# S7G7_footprint_simplified_w_ethernet_v1p.net
KiCad netlist of a schematic drawn in EAGLE
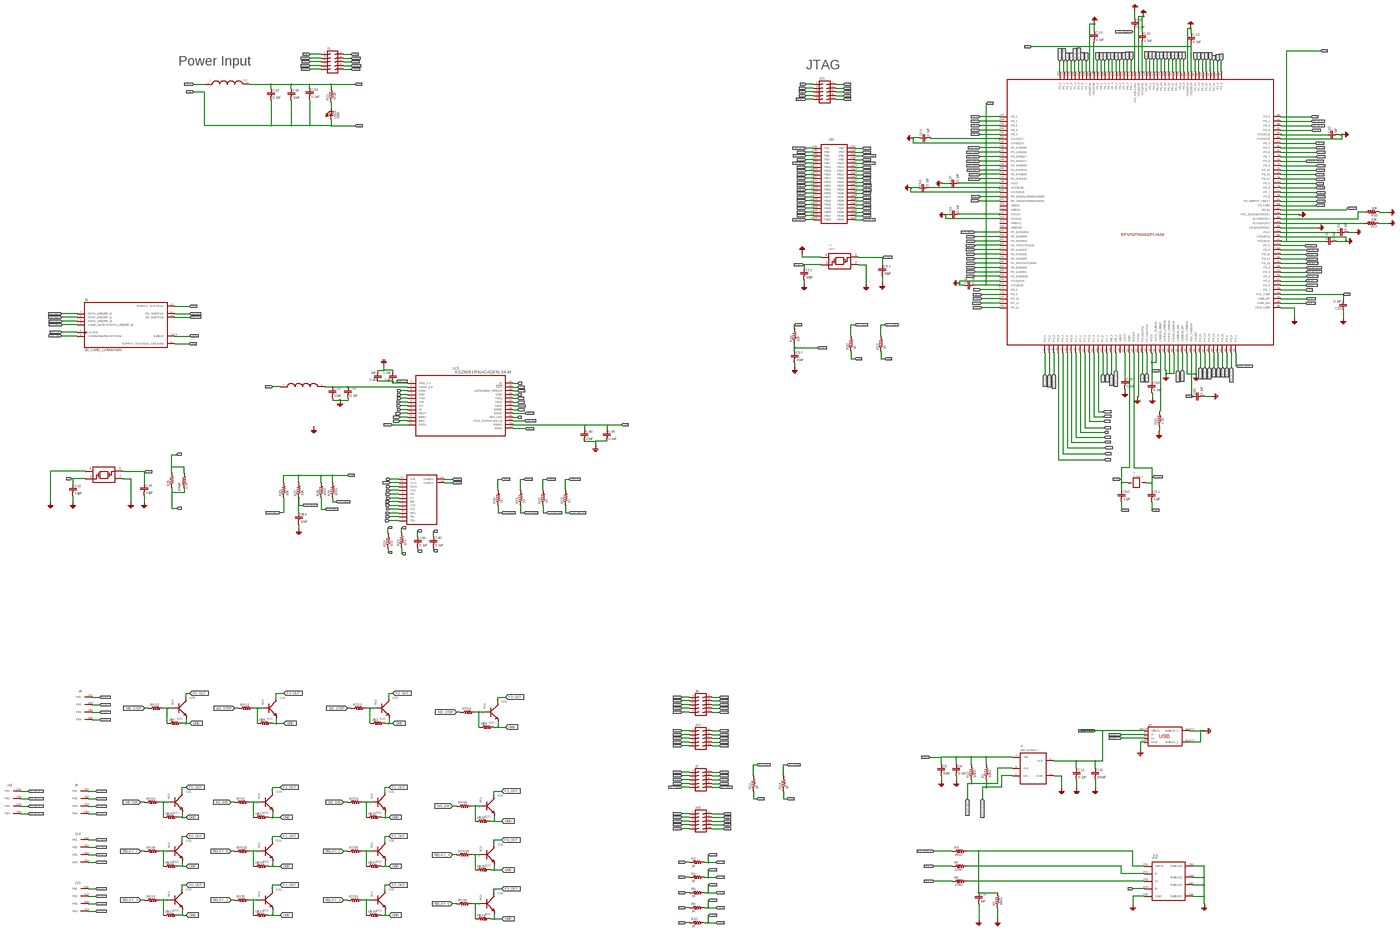
[diagram p0: schematic, sheet 1, overview]
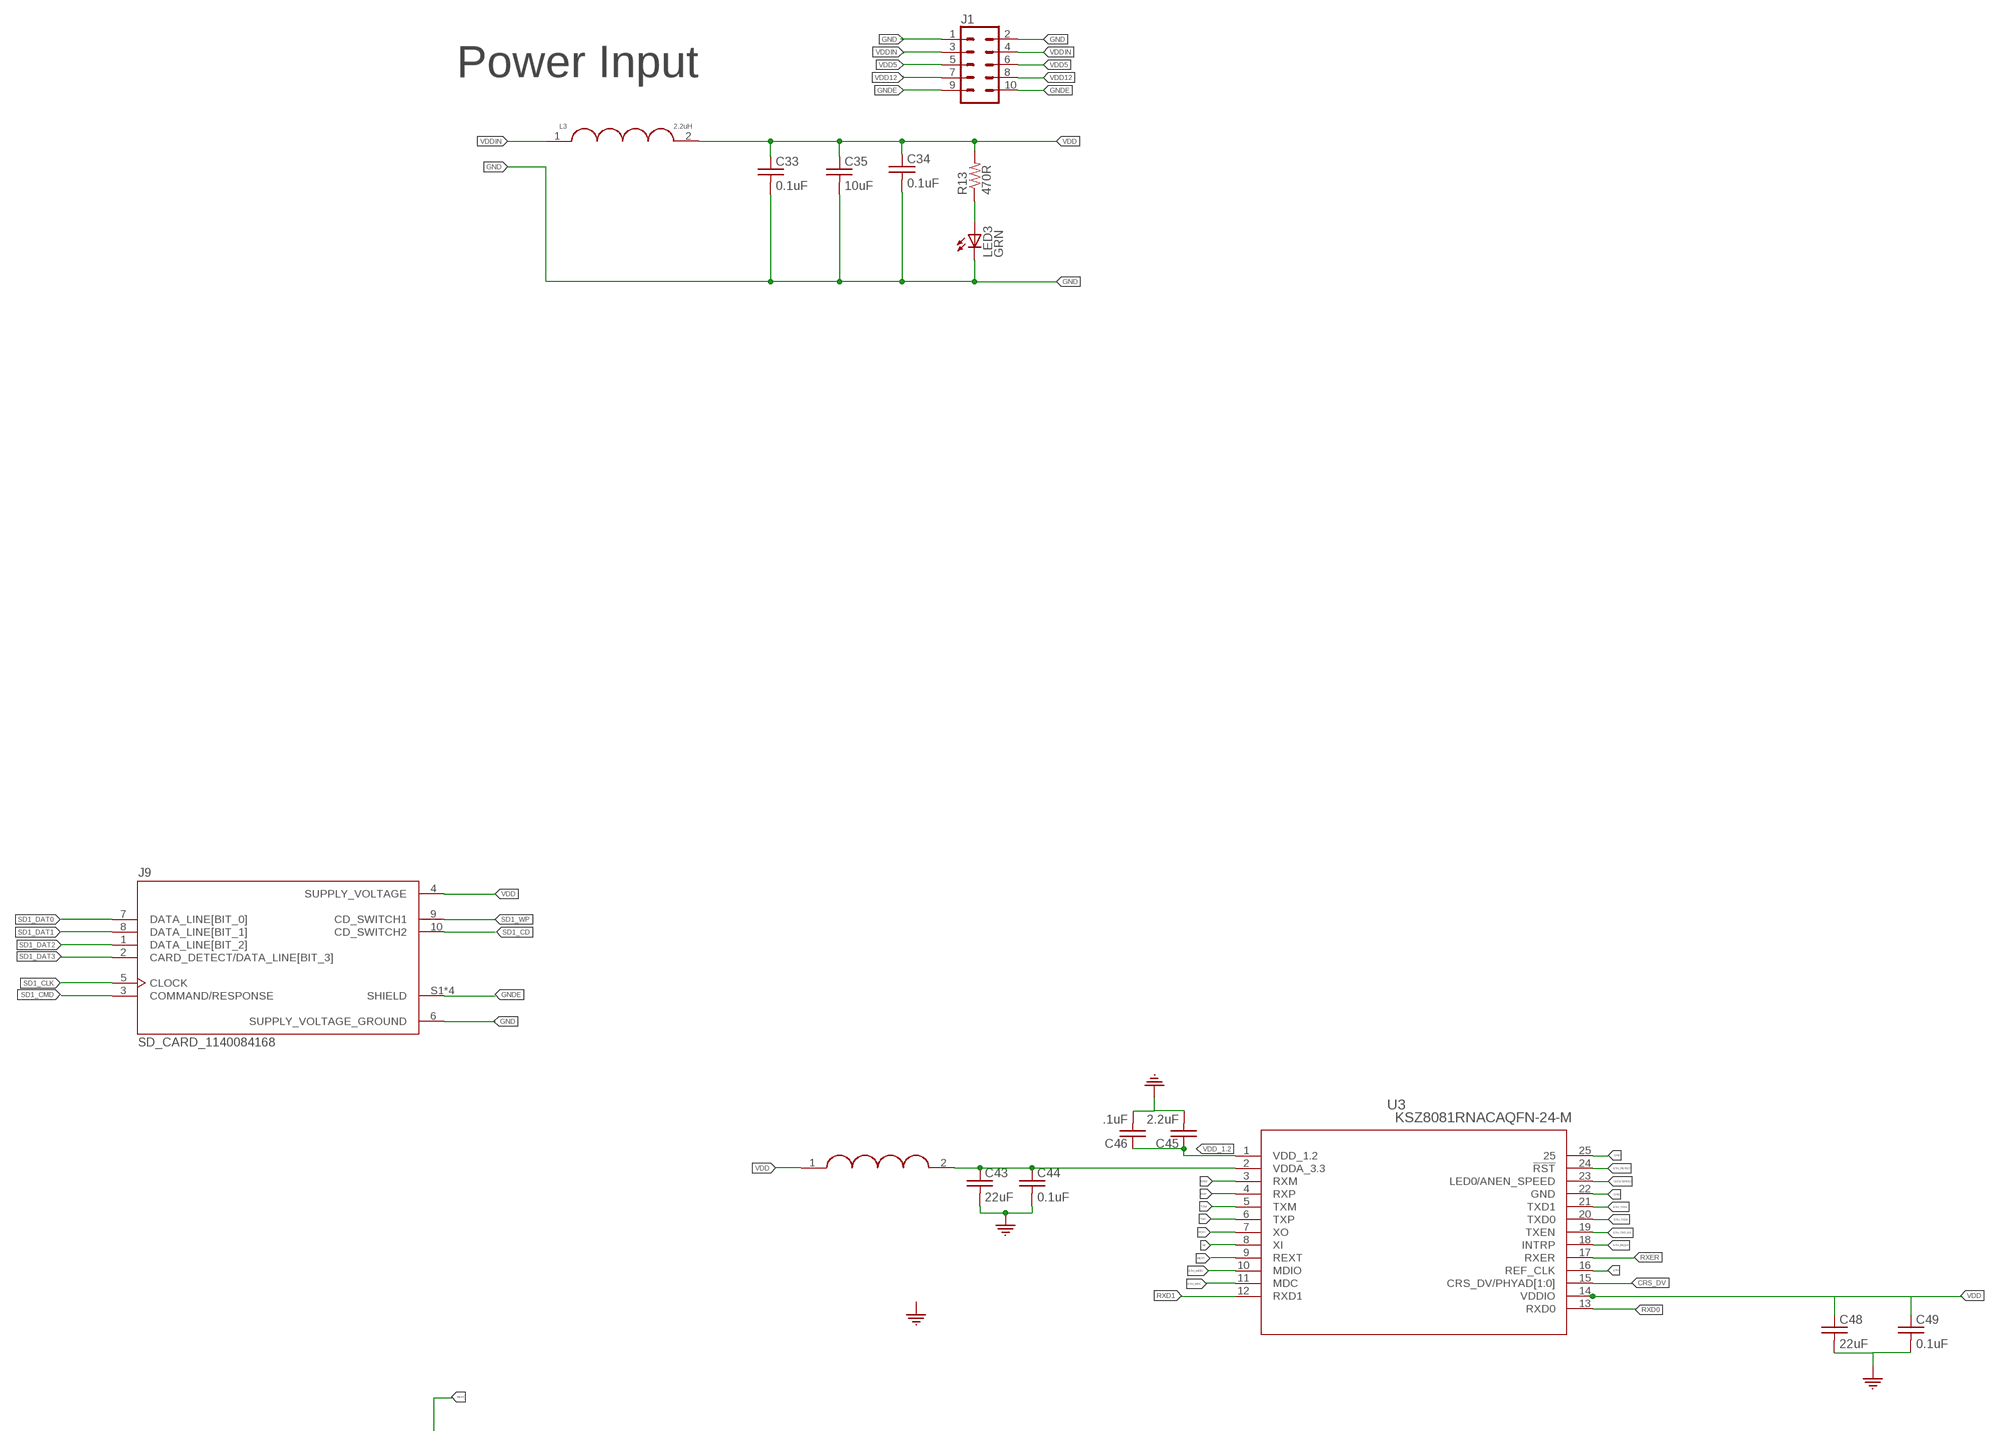
[diagram p1: schematic, sheet 1, part 1 of 4]
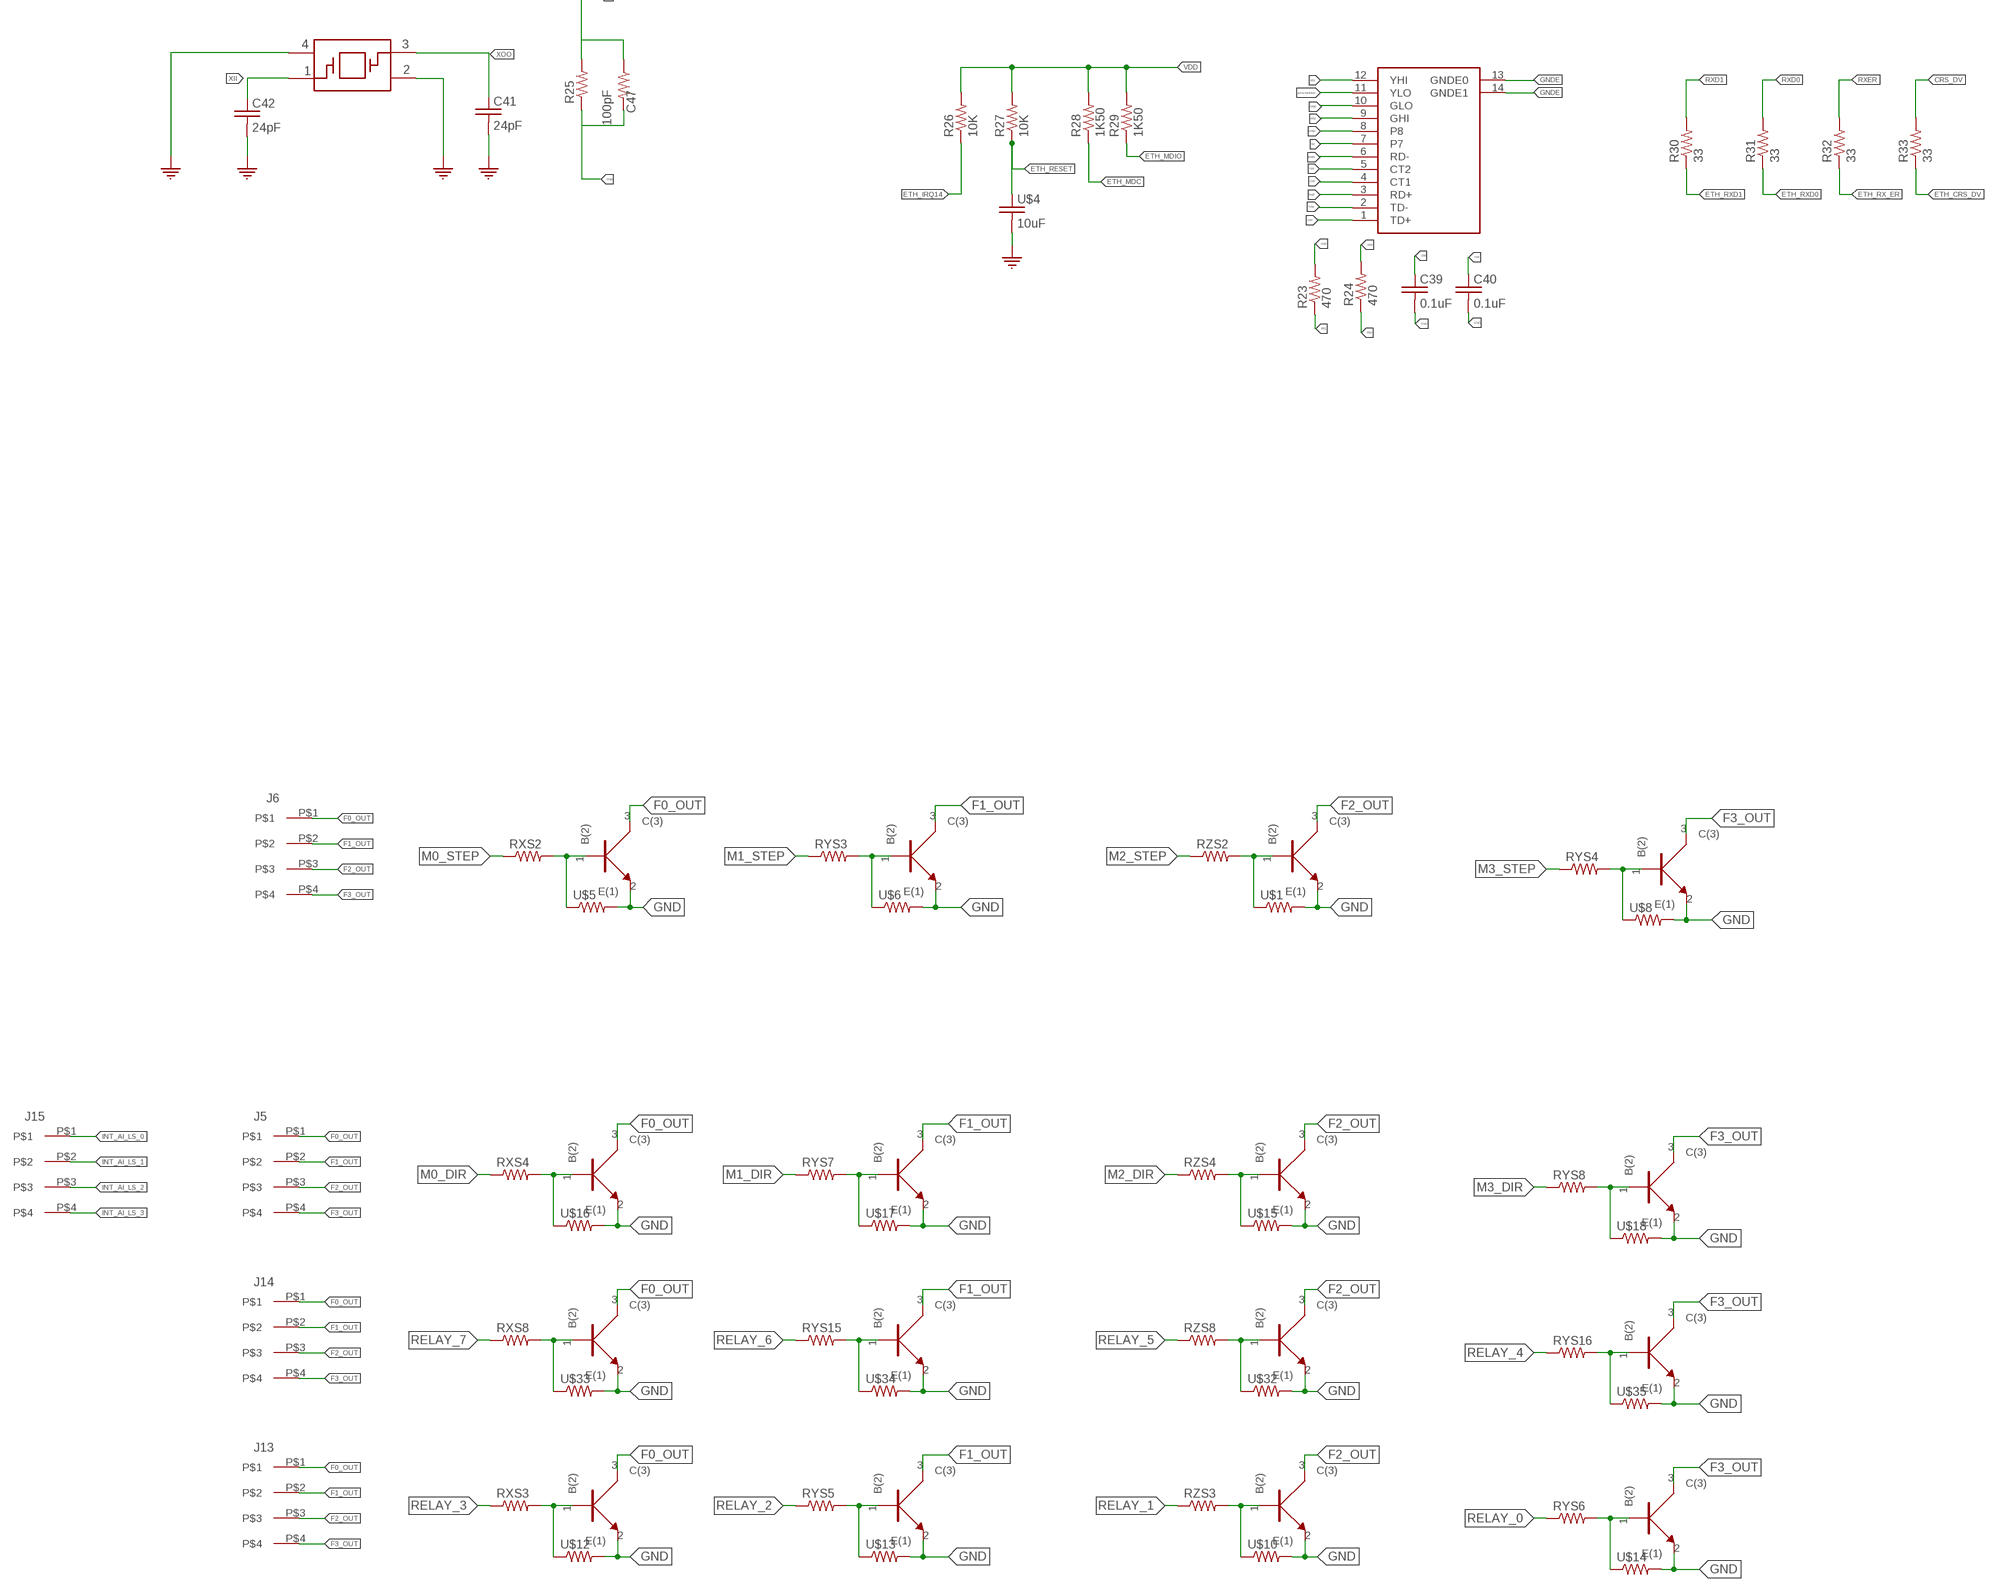
[diagram p2: schematic, sheet 1, part 2 of 4]
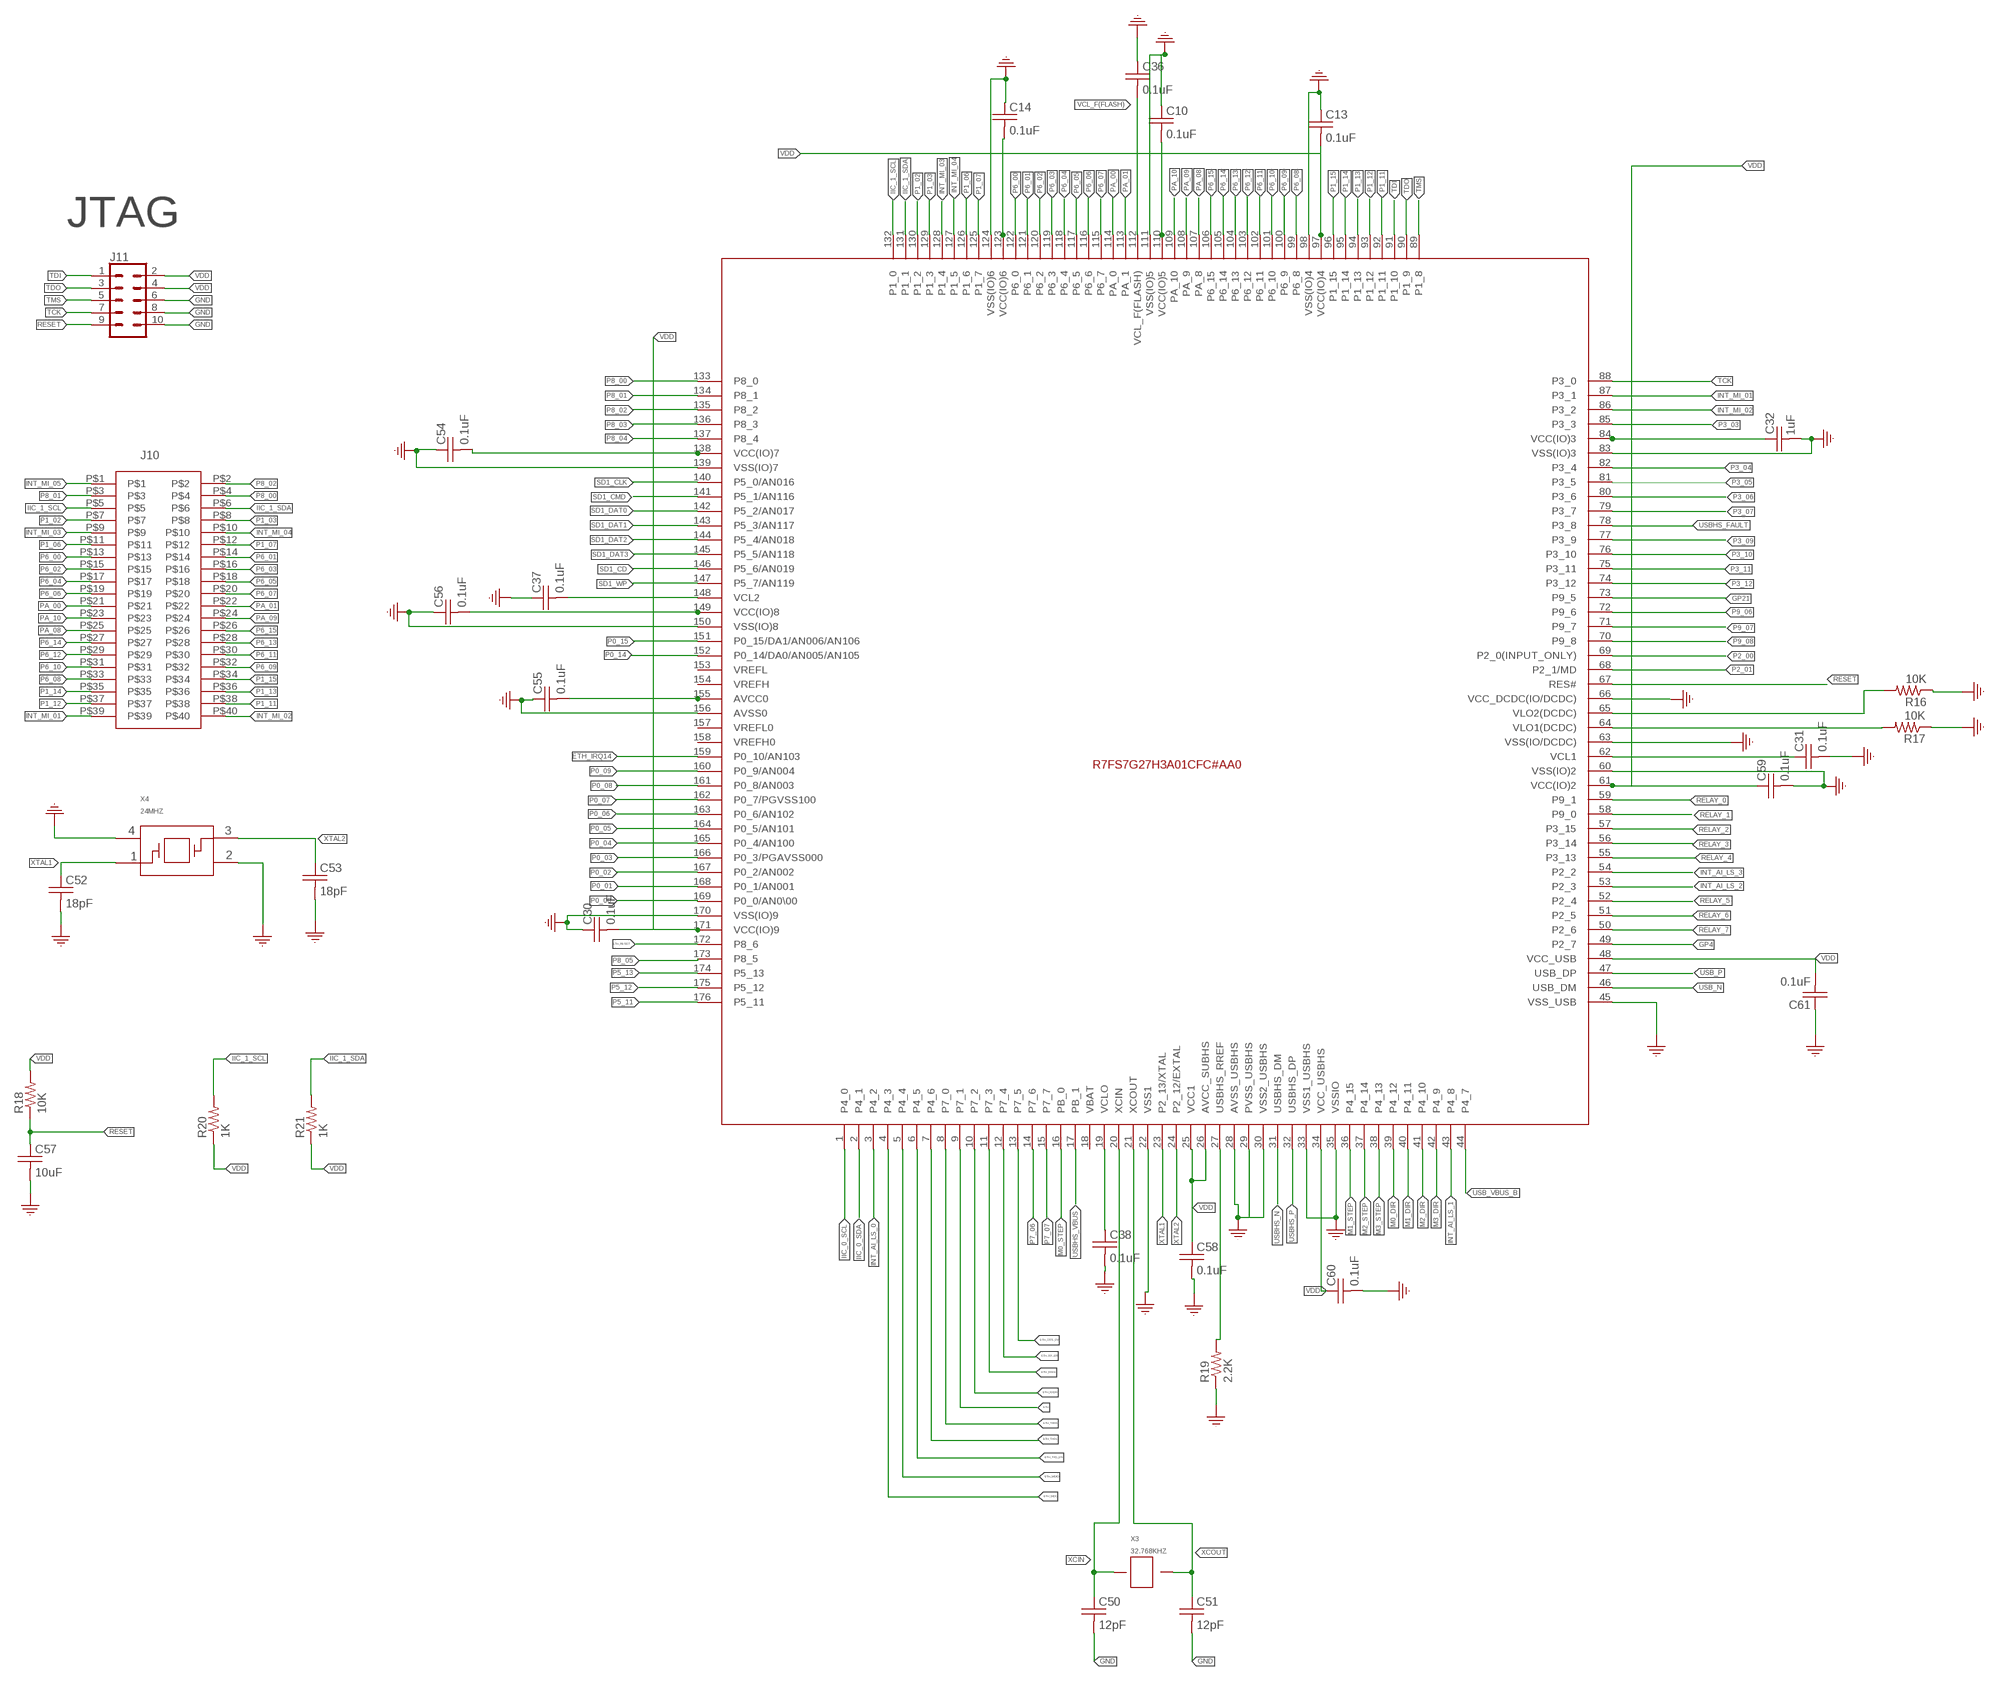
[diagram p3: schematic, sheet 1, part 3 of 4]
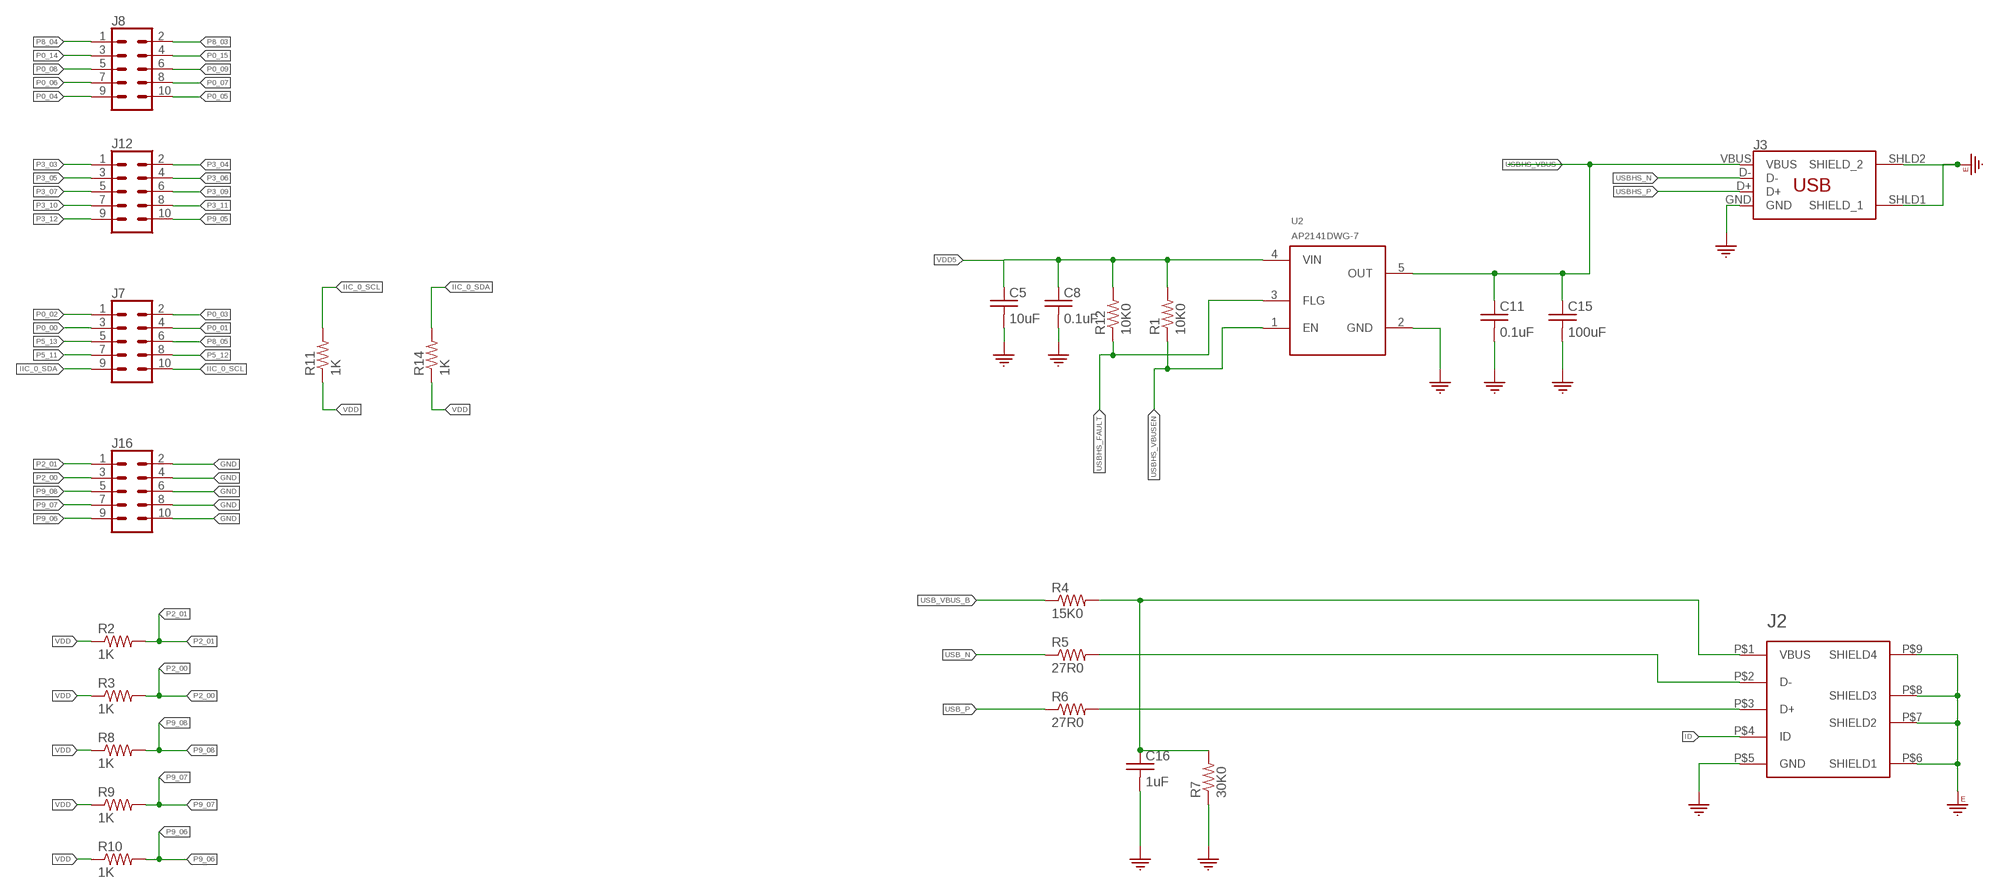
[diagram p4: schematic, sheet 1, part 4 of 4]

(export (version "E")
  (design (tool "Eeschema 10.0.6"))
  (components
    (comp (ref "C5")
      (value "10uF")
      (footprint "eagle-import:0402")
      (libsource (lib "eagle-import") (part "C_0402"))
    )
    (comp (ref "C8")
      (value "0.1uF")
      (footprint "eagle-import:0402")
      (libsource (lib "eagle-import") (part "C_0402"))
    )
    (comp (ref "C10")
      (value "0.1uF")
      (footprint "eagle-import:0402")
      (libsource (lib "eagle-import") (part "C_0402"))
    )
    (comp (ref "C11")
      (value "0.1uF")
      (footprint "eagle-import:0402")
      (libsource (lib "eagle-import") (part "C_0402"))
    )
    (comp (ref "C13")
      (value "0.1uF")
      (footprint "eagle-import:0402")
      (libsource (lib "eagle-import") (part "C_0402"))
    )
    (comp (ref "C14")
      (value "0.1uF")
      (footprint "eagle-import:0402")
      (libsource (lib "eagle-import") (part "C_0402"))
    )
    (comp (ref "C15")
      (value "100uF")
      (footprint "eagle-import:C1210")
      (libsource (lib "eagle-import") (part "C_1210"))
    )
    (comp (ref "C16")
      (value "1uF")
      (footprint "eagle-import:0402")
      (libsource (lib "eagle-import") (part "C_0402"))
    )
    (comp (ref "C30")
      (value "0.1uF")
      (footprint "eagle-import:0402")
      (libsource (lib "eagle-import") (part "C_0402"))
    )
    (comp (ref "C31")
      (value "0.1uF")
      (footprint "eagle-import:0402")
      (libsource (lib "eagle-import") (part "C_0402"))
    )
    (comp (ref "C32")
      (value "1uF")
      (footprint "eagle-import:0402")
      (libsource (lib "eagle-import") (part "C_0402"))
    )
    (comp (ref "C33")
      (value "0.1uF")
      (footprint "eagle-import:0402")
      (libsource (lib "eagle-import") (part "C_0402"))
    )
    (comp (ref "C34")
      (value "0.1uF")
      (footprint "eagle-import:0402")
      (libsource (lib "eagle-import") (part "C_0402"))
    )
    (comp (ref "C35")
      (value "10uF")
      (footprint "eagle-import:0402")
      (libsource (lib "eagle-import") (part "C_0402"))
    )
    (comp (ref "C36")
      (value "0.1uF")
      (footprint "eagle-import:0402")
      (libsource (lib "eagle-import") (part "C_0402"))
    )
    (comp (ref "C37")
      (value "0.1uF")
      (footprint "eagle-import:0402")
      (libsource (lib "eagle-import") (part "C_0402"))
    )
    (comp (ref "C38")
      (value "0.1uF")
      (footprint "eagle-import:0402")
      (libsource (lib "eagle-import") (part "C_0402"))
    )
    (comp (ref "C39")
      (value "0.1uF")
      (footprint "eagle-import:0402")
      (libsource (lib "eagle-import") (part "C_0402"))
    )
    (comp (ref "C40")
      (value "0.1uF")
      (footprint "eagle-import:0402")
      (libsource (lib "eagle-import") (part "C_0402"))
    )
    (comp (ref "C41")
      (value "24pF")
      (footprint "eagle-import:0402")
      (libsource (lib "eagle-import") (part "C_0402"))
    )
    (comp (ref "C42")
      (value "24pF")
      (footprint "eagle-import:0402")
      (libsource (lib "eagle-import") (part "C_0402"))
    )
    (comp (ref "C43")
      (value "22uF")
      (footprint "eagle-import:0603")
      (libsource (lib "eagle-import") (part "C_0603"))
    )
    (comp (ref "C44")
      (value "0.1uF")
      (footprint "eagle-import:0402")
      (libsource (lib "eagle-import") (part "C_0402"))
    )
    (comp (ref "C45")
      (value "2.2uF")
      (footprint "eagle-import:0402")
      (libsource (lib "eagle-import") (part "C_0402"))
    )
    (comp (ref "C46")
      (value ".1uF")
      (footprint "eagle-import:0402")
      (libsource (lib "eagle-import") (part "C_0402"))
    )
    (comp (ref "C47")
      (value "100pF")
      (footprint "eagle-import:0402")
      (libsource (lib "eagle-import") (part "R_0402"))
    )
    (comp (ref "C48")
      (value "22uF")
      (footprint "eagle-import:0603")
      (libsource (lib "eagle-import") (part "C_0603"))
    )
    (comp (ref "C49")
      (value "0.1uF")
      (footprint "eagle-import:0402")
      (libsource (lib "eagle-import") (part "C_0402"))
    )
    (comp (ref "C50")
      (value "12pF")
      (footprint "eagle-import:0402")
      (libsource (lib "eagle-import") (part "C_0402"))
    )
    (comp (ref "C51")
      (value "12pF")
      (footprint "eagle-import:0402")
      (libsource (lib "eagle-import") (part "C_0402"))
    )
    (comp (ref "C52")
      (value "18pF")
      (footprint "eagle-import:0402")
      (libsource (lib "eagle-import") (part "C_0402"))
    )
    (comp (ref "C53")
      (value "18pF")
      (footprint "eagle-import:0402")
      (libsource (lib "eagle-import") (part "C_0402"))
    )
    (comp (ref "C54")
      (value "0.1uF")
      (footprint "eagle-import:0402")
      (libsource (lib "eagle-import") (part "C_0402"))
    )
    (comp (ref "C55")
      (value "0.1uF")
      (footprint "eagle-import:0402")
      (libsource (lib "eagle-import") (part "C_0402"))
    )
    (comp (ref "C56")
      (value "0.1uF")
      (footprint "eagle-import:0402")
      (libsource (lib "eagle-import") (part "C_0402"))
    )
    (comp (ref "C57")
      (value "10uF")
      (footprint "eagle-import:0402")
      (libsource (lib "eagle-import") (part "C_0402"))
    )
    (comp (ref "C58")
      (value "0.1uF")
      (footprint "eagle-import:0402")
      (libsource (lib "eagle-import") (part "C_0402"))
    )
    (comp (ref "C59")
      (value "0.1uF")
      (footprint "eagle-import:0402")
      (libsource (lib "eagle-import") (part "C_0402"))
    )
    (comp (ref "C60")
      (value "0.1uF")
      (footprint "eagle-import:0402")
      (libsource (lib "eagle-import") (part "C_0402"))
    )
    (comp (ref "C61")
      (value "0.1uF")
      (footprint "eagle-import:0402")
      (libsource (lib "eagle-import") (part "C_0402"))
    )
    (comp (ref "FB2/2")
      (value "FB_0805_120_OHM")
      (footprint "eagle-import:0805")
      (libsource (lib "eagle-import") (part "FB_0805_120_OHM"))
    )
    (comp (ref "J1")
      (value "CONN_05X2PTH")
      (footprint "eagle-import:2X5")
      (libsource (lib "eagle-import") (part "CONN_05X2PTH"))
    )
    (comp (ref "J2")
      (value "USB_MICRO-B")
      (footprint "eagle-import:USB_MICRO-B")
      (libsource (lib "eagle-import") (part "USB_MICRO-B"))
    )
    (comp (ref "J3")
      (value "USB_A")
      (footprint "eagle-import:USB_A_SMT")
      (libsource (lib "eagle-import") (part "USB_A"))
    )
    (comp (ref "J4")
      (value "RJ45_WITH_ELEC")
      (footprint "eagle-import:RJ45_TH_ELEC")
      (libsource (lib "eagle-import") (part "RJ45_WITH_ELEC"))
    )
    (comp (ref "J5")
      (value "3.81MM_1_X_4_RT_ANGLE_PLUG_HEADER")
      (footprint "eagle-import:1X4_3.81MM_PITCH")
      (libsource (lib "eagle-import") (part "3.81MM_1_X_4_RT_ANGLE_PLUG_HEADER"))
    )
    (comp (ref "J6")
      (value "3.81MM_1_X_4_RT_ANGLE_PLUG_HEADER")
      (footprint "eagle-import:1X4_3.81MM_PITCH")
      (libsource (lib "eagle-import") (part "3.81MM_1_X_4_RT_ANGLE_PLUG_HEADER"))
    )
    (comp (ref "J7")
      (value "CONN_05X2NO_SILK")
      (footprint "eagle-import:2X5_NOSILK")
      (libsource (lib "eagle-import") (part "CONN_05X2NO_SILK"))
    )
    (comp (ref "J8")
      (value "CONN_05X2NO_SILK")
      (footprint "eagle-import:2X5_NOSILK")
      (libsource (lib "eagle-import") (part "CONN_05X2NO_SILK"))
    )
    (comp (ref "J9")
      (value "SD_CARD_1140084168")
      (footprint "eagle-import:AMPHENOL_1140084168")
      (fields
        (field (name "DIGI-KEY_PART_NUMBER") "114-00841-68-1-ND")
        (field (name "MF") "Amphenol ICC")
        (field (name "MP") "114-00841-68")
      )
      (libsource (lib "eagle-import") (part "SD_CARD_1140084168"))
    )
    (comp (ref "J10")
      (value "HEADER_2_X_20_GENERIC")
      (footprint "eagle-import:HEADER_2_X_20_.1_INCH")
      (libsource (lib "eagle-import") (part "HEADER_2_X_20_GENERIC"))
    )
    (comp (ref "J11")
      (value "CONN_05X2PTH")
      (footprint "eagle-import:2X5")
      (libsource (lib "eagle-import") (part "CONN_05X2PTH"))
    )
    (comp (ref "J12")
      (value "CONN_05X2NO_SILK")
      (footprint "eagle-import:2X5_NOSILK")
      (libsource (lib "eagle-import") (part "CONN_05X2NO_SILK"))
    )
    (comp (ref "J13")
      (value "3.81MM_1_X_4_RT_ANGLE_PLUG_HEADER")
      (footprint "eagle-import:1X4_3.81MM_PITCH")
      (libsource (lib "eagle-import") (part "3.81MM_1_X_4_RT_ANGLE_PLUG_HEADER"))
    )
    (comp (ref "J14")
      (value "3.81MM_1_X_4_RT_ANGLE_PLUG_HEADER")
      (footprint "eagle-import:1X4_3.81MM_PITCH")
      (libsource (lib "eagle-import") (part "3.81MM_1_X_4_RT_ANGLE_PLUG_HEADER"))
    )
    (comp (ref "J15")
      (value "3.81MM_1_X_4_RT_ANGLE_PLUG_HEADER")
      (footprint "eagle-import:1X4_3.81MM_PITCH")
      (libsource (lib "eagle-import") (part "3.81MM_1_X_4_RT_ANGLE_PLUG_HEADER"))
    )
    (comp (ref "J16")
      (value "CONN_05X2SHD_SMD")
      (footprint "eagle-import:2X5-SHROUDED_SMD")
      (libsource (lib "eagle-import") (part "CONN_05X2SHD_SMD"))
    )
    (comp (ref "L3")
      (value "2.2uH")
      (footprint "eagle-import:1008_(2520_METRIC)")
      (libsource (lib "eagle-import") (part "INDUCTOR_1008_2.2_MH_1.3A"))
    )
    (comp (ref "LED3")
      (value "LED_0805_GREEN")
      (footprint "eagle-import:LED_0805_GREEN")
      (libsource (lib "eagle-import") (part "LED_0805_GREEN"))
    )
    (comp (ref "R1")
      (value "10K0")
      (footprint "eagle-import:0402")
      (libsource (lib "eagle-import") (part "R_0402"))
    )
    (comp (ref "R2")
      (value "1K")
      (footprint "eagle-import:0402")
      (libsource (lib "eagle-import") (part "R_0402"))
    )
    (comp (ref "R3")
      (value "1K")
      (footprint "eagle-import:0402")
      (libsource (lib "eagle-import") (part "R_0402"))
    )
    (comp (ref "R4")
      (value "15K0")
      (footprint "eagle-import:0402")
      (libsource (lib "eagle-import") (part "R_0402"))
    )
    (comp (ref "R5")
      (value "27R0")
      (footprint "eagle-import:0402")
      (libsource (lib "eagle-import") (part "R_0402"))
    )
    (comp (ref "R6")
      (value "27R0")
      (footprint "eagle-import:0402")
      (libsource (lib "eagle-import") (part "R_0402"))
    )
    (comp (ref "R7")
      (value "30K0")
      (footprint "eagle-import:0402")
      (libsource (lib "eagle-import") (part "R_0402"))
    )
    (comp (ref "R8")
      (value "1K")
      (footprint "eagle-import:0402")
      (libsource (lib "eagle-import") (part "R_0402"))
    )
    (comp (ref "R9")
      (value "1K")
      (footprint "eagle-import:0402")
      (libsource (lib "eagle-import") (part "R_0402"))
    )
    (comp (ref "R10")
      (value "1K")
      (footprint "eagle-import:0402")
      (libsource (lib "eagle-import") (part "R_0402"))
    )
    (comp (ref "R11")
      (value "1K")
      (footprint "eagle-import:0402")
      (libsource (lib "eagle-import") (part "R_0402"))
    )
    (comp (ref "R12")
      (value "10K0")
      (footprint "eagle-import:0402")
      (libsource (lib "eagle-import") (part "R_0402"))
    )
    (comp (ref "R13")
      (value "470R")
      (footprint "eagle-import:0402")
      (libsource (lib "eagle-import") (part "R_0402"))
    )
    (comp (ref "R14")
      (value "1K")
      (footprint "eagle-import:0402")
      (libsource (lib "eagle-import") (part "R_0402"))
    )
    (comp (ref "R16")
      (value "10K")
      (footprint "eagle-import:0402")
      (libsource (lib "eagle-import") (part "R_0402"))
    )
    (comp (ref "R17")
      (value "10K")
      (footprint "eagle-import:0402")
      (libsource (lib "eagle-import") (part "R_0402"))
    )
    (comp (ref "R18")
      (value "10K")
      (footprint "eagle-import:0402")
      (libsource (lib "eagle-import") (part "R_0402"))
    )
    (comp (ref "R19")
      (value "2.2K")
      (footprint "eagle-import:0402")
      (libsource (lib "eagle-import") (part "R_0402"))
    )
    (comp (ref "R20")
      (value "1K")
      (footprint "eagle-import:0402")
      (libsource (lib "eagle-import") (part "R_0402"))
    )
    (comp (ref "R21")
      (value "1K")
      (footprint "eagle-import:0402")
      (libsource (lib "eagle-import") (part "R_0402"))
    )
    (comp (ref "R23")
      (value "470")
      (footprint "eagle-import:0402")
      (libsource (lib "eagle-import") (part "R_0402"))
    )
    (comp (ref "R24")
      (value "470")
      (footprint "eagle-import:0402")
      (libsource (lib "eagle-import") (part "R_0402"))
    )
    (comp (ref "R25")
      (value "6k49")
      (footprint "eagle-import:0402")
      (libsource (lib "eagle-import") (part "R_0402"))
    )
    (comp (ref "R26")
      (value "10K")
      (footprint "eagle-import:0402")
      (libsource (lib "eagle-import") (part "R_0402"))
    )
    (comp (ref "R27")
      (value "10K")
      (footprint "eagle-import:0402")
      (libsource (lib "eagle-import") (part "R_0402"))
    )
    (comp (ref "R28")
      (value "1K50")
      (footprint "eagle-import:0402")
      (libsource (lib "eagle-import") (part "R_0402"))
    )
    (comp (ref "R29")
      (value "1K50")
      (footprint "eagle-import:0402")
      (libsource (lib "eagle-import") (part "R_0402"))
    )
    (comp (ref "R30")
      (value "33")
      (footprint "eagle-import:0402")
      (libsource (lib "eagle-import") (part "R_0402"))
    )
    (comp (ref "R31")
      (value "33")
      (footprint "eagle-import:0402")
      (libsource (lib "eagle-import") (part "R_0402"))
    )
    (comp (ref "R32")
      (value "33")
      (footprint "eagle-import:0402")
      (libsource (lib "eagle-import") (part "R_0402"))
    )
    (comp (ref "R33")
      (value "33")
      (footprint "eagle-import:0402")
      (libsource (lib "eagle-import") (part "R_0402"))
    )
    (comp (ref "RXS2")
      (value "1K")
      (footprint "eagle-import:0402")
      (libsource (lib "eagle-import") (part "R_0402"))
    )
    (comp (ref "RXS3")
      (value "1K")
      (footprint "eagle-import:0402")
      (libsource (lib "eagle-import") (part "R_0402"))
    )
    (comp (ref "RXS4")
      (value "1K")
      (footprint "eagle-import:0402")
      (libsource (lib "eagle-import") (part "R_0402"))
    )
    (comp (ref "RXS8")
      (value "1K")
      (footprint "eagle-import:0402")
      (libsource (lib "eagle-import") (part "R_0402"))
    )
    (comp (ref "RYS3")
      (value "1K")
      (footprint "eagle-import:0402")
      (libsource (lib "eagle-import") (part "R_0402"))
    )
    (comp (ref "RYS4")
      (value "1K")
      (footprint "eagle-import:0402")
      (libsource (lib "eagle-import") (part "R_0402"))
    )
    (comp (ref "RYS5")
      (value "1K")
      (footprint "eagle-import:0402")
      (libsource (lib "eagle-import") (part "R_0402"))
    )
    (comp (ref "RYS6")
      (value "1K")
      (footprint "eagle-import:0402")
      (libsource (lib "eagle-import") (part "R_0402"))
    )
    (comp (ref "RYS7")
      (value "1K")
      (footprint "eagle-import:0402")
      (libsource (lib "eagle-import") (part "R_0402"))
    )
    (comp (ref "RYS8")
      (value "1K")
      (footprint "eagle-import:0402")
      (libsource (lib "eagle-import") (part "R_0402"))
    )
    (comp (ref "RYS15")
      (value "1K")
      (footprint "eagle-import:0402")
      (libsource (lib "eagle-import") (part "R_0402"))
    )
    (comp (ref "RYS16")
      (value "1K")
      (footprint "eagle-import:0402")
      (libsource (lib "eagle-import") (part "R_0402"))
    )
    (comp (ref "RZS2")
      (value "1K")
      (footprint "eagle-import:0402")
      (libsource (lib "eagle-import") (part "R_0402"))
    )
    (comp (ref "RZS3")
      (value "1K")
      (footprint "eagle-import:0402")
      (libsource (lib "eagle-import") (part "R_0402"))
    )
    (comp (ref "RZS4")
      (value "1K")
      (footprint "eagle-import:0402")
      (libsource (lib "eagle-import") (part "R_0402"))
    )
    (comp (ref "RZS8")
      (value "1K")
      (footprint "eagle-import:0402")
      (libsource (lib "eagle-import") (part "R_0402"))
    )
    (comp (ref "U$1")
      (value "1K")
      (footprint "eagle-import:0402")
      (libsource (lib "eagle-import") (part "R_0402"))
    )
    (comp (ref "U$3")
      (value "XTAL_25_MHZ")
      (footprint "eagle-import:SMD_3225")
      (libsource (lib "eagle-import") (part "XTAL_25_MHZ"))
    )
    (comp (ref "U$4")
      (value "10uF")
      (footprint "eagle-import:0402")
      (libsource (lib "eagle-import") (part "C_0402"))
    )
    (comp (ref "U$5")
      (value "1K")
      (footprint "eagle-import:0402")
      (libsource (lib "eagle-import") (part "R_0402"))
    )
    (comp (ref "U$6")
      (value "1K")
      (footprint "eagle-import:0402")
      (libsource (lib "eagle-import") (part "R_0402"))
    )
    (comp (ref "U$8")
      (value "1K")
      (footprint "eagle-import:0402")
      (libsource (lib "eagle-import") (part "R_0402"))
    )
    (comp (ref "U$10")
      (value "1K")
      (footprint "eagle-import:0402")
      (libsource (lib "eagle-import") (part "R_0402"))
    )
    (comp (ref "U$12")
      (value "1K")
      (footprint "eagle-import:0402")
      (libsource (lib "eagle-import") (part "R_0402"))
    )
    (comp (ref "U$13")
      (value "1K")
      (footprint "eagle-import:0402")
      (libsource (lib "eagle-import") (part "R_0402"))
    )
    (comp (ref "U$14")
      (value "1K")
      (footprint "eagle-import:0402")
      (libsource (lib "eagle-import") (part "R_0402"))
    )
    (comp (ref "U$15")
      (value "1K")
      (footprint "eagle-import:0402")
      (libsource (lib "eagle-import") (part "R_0402"))
    )
    (comp (ref "U$16")
      (value "1K")
      (footprint "eagle-import:0402")
      (libsource (lib "eagle-import") (part "R_0402"))
    )
    (comp (ref "U$17")
      (value "1K")
      (footprint "eagle-import:0402")
      (libsource (lib "eagle-import") (part "R_0402"))
    )
    (comp (ref "U$18")
      (value "1K")
      (footprint "eagle-import:0402")
      (libsource (lib "eagle-import") (part "R_0402"))
    )
    (comp (ref "U$32")
      (value "1K")
      (footprint "eagle-import:0402")
      (libsource (lib "eagle-import") (part "R_0402"))
    )
    (comp (ref "U$33")
      (value "1K")
      (footprint "eagle-import:0402")
      (libsource (lib "eagle-import") (part "R_0402"))
    )
    (comp (ref "U$34")
      (value "1K")
      (footprint "eagle-import:0402")
      (libsource (lib "eagle-import") (part "R_0402"))
    )
    (comp (ref "U$35")
      (value "1K")
      (footprint "eagle-import:0402")
      (libsource (lib "eagle-import") (part "R_0402"))
    )
    (comp (ref "U2")
      (value "AP2141DWG-5")
      (footprint "eagle-import:SOT-23-5")
      (libsource (lib "eagle-import") (part "AP2141DWG-5"))
    )
    (comp (ref "U3")
      (value "KSZ8081RNACAQFN-24-M")
      (footprint "eagle-import:QFN-24-M")
      (fields (field (name "MANUFACTURER_PART_NUMBER") "KSZ8081RNACA"))
      (libsource (lib "eagle-import") (part "KSZ8081RNACAQFN-24-M"))
    )
    (comp (ref "U4")
      (value "S7G2_X_176")
      (footprint "eagle-import:LQFP176_24X24")
      (libsource (lib "eagle-import") (part "S7G2_X_176"))
    )
    (comp (ref "U7")
      (value "BC846BW")
      (footprint "eagle-import:SOT323")
      (libsource (lib "eagle-import") (part "BC846BW"))
    )
    (comp (ref "U8")
      (value "BC846BW")
      (footprint "eagle-import:SOT323")
      (libsource (lib "eagle-import") (part "BC846BW"))
    )
    (comp (ref "U9")
      (value "BC846BW")
      (footprint "eagle-import:SOT323")
      (libsource (lib "eagle-import") (part "BC846BW"))
    )
    (comp (ref "U10")
      (value "BC846BW")
      (footprint "eagle-import:SOT323")
      (libsource (lib "eagle-import") (part "BC846BW"))
    )
    (comp (ref "U12")
      (value "BC846BW")
      (footprint "eagle-import:SOT323")
      (libsource (lib "eagle-import") (part "BC846BW"))
    )
    (comp (ref "U13")
      (value "BC846BW")
      (footprint "eagle-import:SOT323")
      (libsource (lib "eagle-import") (part "BC846BW"))
    )
    (comp (ref "U14")
      (value "BC846BW")
      (footprint "eagle-import:SOT323")
      (libsource (lib "eagle-import") (part "BC846BW"))
    )
    (comp (ref "U15")
      (value "BC846BW")
      (footprint "eagle-import:SOT323")
      (libsource (lib "eagle-import") (part "BC846BW"))
    )
    (comp (ref "U16")
      (value "BC846BW")
      (footprint "eagle-import:SOT323")
      (libsource (lib "eagle-import") (part "BC846BW"))
    )
    (comp (ref "U17")
      (value "BC846BW")
      (footprint "eagle-import:SOT323")
      (libsource (lib "eagle-import") (part "BC846BW"))
    )
    (comp (ref "U18")
      (value "BC846BW")
      (footprint "eagle-import:SOT323")
      (libsource (lib "eagle-import") (part "BC846BW"))
    )
    (comp (ref "U19")
      (value "BC846BW")
      (footprint "eagle-import:SOT323")
      (libsource (lib "eagle-import") (part "BC846BW"))
    )
    (comp (ref "U32")
      (value "BC846BW")
      (footprint "eagle-import:SOT323")
      (libsource (lib "eagle-import") (part "BC846BW"))
    )
    (comp (ref "U33")
      (value "BC846BW")
      (footprint "eagle-import:SOT323")
      (libsource (lib "eagle-import") (part "BC846BW"))
    )
    (comp (ref "U34")
      (value "BC846BW")
      (footprint "eagle-import:SOT323")
      (libsource (lib "eagle-import") (part "BC846BW"))
    )
    (comp (ref "U35")
      (value "BC846BW")
      (footprint "eagle-import:SOT323")
      (libsource (lib "eagle-import") (part "BC846BW"))
    )
    (comp (ref "X3")
      (value "32.768KHZ")
      (footprint "eagle-import:SMD_X_2_PADS")
      (libsource (lib "eagle-import") (part "XTAL_32.768KHZ"))
    )
    (comp (ref "X4")
      (value "24MHZ")
      (footprint "eagle-import:SMD_3225")
      (libsource (lib "eagle-import") (part "XTAL_24_MHZ"))
    )
  )
  (nets
    (net (code "1") (name "C58") (class "Default")
      (node (ref "C39") (pin "P$1") (pinfunction "1_P$1") (pintype "passive"))
      (node (ref "J4") (pin "4") (pinfunction "CT1_4") (pintype "bidirectional"))
    )
    (net (code "2") (name "C60") (class "Default")
      (node (ref "C40") (pin "P$1") (pinfunction "1_P$1") (pintype "passive"))
      (node (ref "J4") (pin "5") (pinfunction "CT2_5") (pintype "bidirectional"))
    )
    (net (code "3") (name "CRS_DV") (class "Default")
      (node (ref "R33") (pin "P$2") (pinfunction "2_P$2") (pintype "passive"))
      (node (ref "U3") (pin "15") (pinfunction "CRS_DV/PHYAD[1:0]_15") (pintype "bidirectional"))
    )
    (net (code "4") (name "ETH") (class "Default")
      (node (ref "U3") (pin "16") (pinfunction "REF_CLK_16") (pintype "bidirectional"))
      (node (ref "U4") (pin "9") (pinfunction "P7_1_9") (pintype "bidirectional"))
    )
    (net (code "5") (name "ETH_CRS_DV") (class "Default")
      (node (ref "R33") (pin "P$1") (pinfunction "1_P$1") (pintype "passive"))
      (node (ref "U4") (pin "13") (pinfunction "P7_5_13") (pintype "bidirectional"))
    )
    (net (code "6") (name "ETH_IRQ14") (class "Default")
      (node (ref "R26") (pin "P$1") (pinfunction "1_P$1") (pintype "passive"))
      (node (ref "U3") (pin "18") (pinfunction "INTRP_18") (pintype "bidirectional"))
      (node (ref "U4") (pin "159") (pinfunction "P0_10/AN103_159") (pintype "bidirectional"))
    )
    (net (code "7") (name "ETH_MDC") (class "Default")
      (node (ref "R28") (pin "P$1") (pinfunction "1_P$1") (pintype "passive"))
      (node (ref "U3") (pin "11") (pinfunction "MDC_11") (pintype "input"))
      (node (ref "U4") (pin "4") (pinfunction "P4_3_4") (pintype "bidirectional"))
    )
    (net (code "8") (name "ETH_MDIO") (class "Default")
      (node (ref "R29") (pin "P$1") (pinfunction "1_P$1") (pintype "passive"))
      (node (ref "U3") (pin "10") (pinfunction "MDIO_10") (pintype "bidirectional"))
      (node (ref "U4") (pin "5") (pinfunction "P4_4_5") (pintype "bidirectional"))
    )
    (net (code "9") (name "ETH_RESET") (class "Default")
      (node (ref "R27") (pin "P$1") (pinfunction "1_P$1") (pintype "passive"))
      (node (ref "U$4") (pin "P$1") (pinfunction "1_P$1") (pintype "passive"))
      (node (ref "U3") (pin "24") (pinfunction "~{RST}_24") (pintype "input"))
      (node (ref "U4") (pin "172") (pinfunction "P8_6_172") (pintype "bidirectional"))
    )
    (net (code "10") (name "ETH_RXD0") (class "Default")
      (node (ref "R31") (pin "P$1") (pinfunction "1_P$1") (pintype "passive"))
      (node (ref "U4") (pin "10") (pinfunction "P7_2_10") (pintype "bidirectional"))
    )
    (net (code "11") (name "ETH_RXD1") (class "Default")
      (node (ref "R30") (pin "P$1") (pinfunction "1_P$1") (pintype "passive"))
      (node (ref "U4") (pin "11") (pinfunction "P7_3_11") (pintype "bidirectional"))
    )
    (net (code "12") (name "ETH_RX_ER") (class "Default")
      (node (ref "R32") (pin "P$1") (pinfunction "1_P$1") (pintype "passive"))
      (node (ref "U4") (pin "12") (pinfunction "P7_4_12") (pintype "bidirectional"))
    )
    (net (code "13") (name "ETH_TXD0") (class "Default")
      (node (ref "U3") (pin "20") (pinfunction "TXD0_20") (pintype "input"))
      (node (ref "U4") (pin "8") (pinfunction "P7_0_8") (pintype "bidirectional"))
    )
    (net (code "14") (name "ETH_TXD1") (class "Default")
      (node (ref "U3") (pin "21") (pinfunction "TXD1_21") (pintype "bidirectional"))
      (node (ref "U4") (pin "7") (pinfunction "P4_6_7") (pintype "bidirectional"))
    )
    (net (code "15") (name "ETH_TXD_EN") (class "Default")
      (node (ref "U3") (pin "19") (pinfunction "TXEN_19") (pintype "input"))
      (node (ref "U4") (pin "6") (pinfunction "P4_5_6") (pintype "bidirectional"))
    )
    (net (code "16") (name "F0_OUT") (class "Default")
      (node (ref "J13") (pin "P$1") (pinfunction "P$1_P$1") (pintype "bidirectional"))
      (node (ref "J14") (pin "P$1") (pinfunction "P$1_P$1") (pintype "bidirectional"))
      (node (ref "J5") (pin "P$1") (pinfunction "P$1_P$1") (pintype "bidirectional"))
      (node (ref "J6") (pin "P$1") (pinfunction "P$1_P$1") (pintype "bidirectional"))
      (node (ref "U13") (pin "3") (pinfunction "C(3)_3") (pintype "input"))
      (node (ref "U17") (pin "3") (pinfunction "C(3)_3") (pintype "input"))
      (node (ref "U33") (pin "3") (pinfunction "C(3)_3") (pintype "input"))
      (node (ref "U8") (pin "3") (pinfunction "C(3)_3") (pintype "input"))
    )
    (net (code "17") (name "F1_OUT") (class "Default")
      (node (ref "J13") (pin "P$2") (pinfunction "P$2_P$2") (pintype "bidirectional"))
      (node (ref "J14") (pin "P$2") (pinfunction "P$2_P$2") (pintype "bidirectional"))
      (node (ref "J5") (pin "P$2") (pinfunction "P$2_P$2") (pintype "bidirectional"))
      (node (ref "J6") (pin "P$2") (pinfunction "P$2_P$2") (pintype "bidirectional"))
      (node (ref "U14") (pin "3") (pinfunction "C(3)_3") (pintype "input"))
      (node (ref "U18") (pin "3") (pinfunction "C(3)_3") (pintype "input"))
      (node (ref "U34") (pin "3") (pinfunction "C(3)_3") (pintype "input"))
      (node (ref "U9") (pin "3") (pinfunction "C(3)_3") (pintype "input"))
    )
    (net (code "18") (name "F2_OUT") (class "Default")
      (node (ref "J13") (pin "P$3") (pinfunction "P$3_P$3") (pintype "bidirectional"))
      (node (ref "J14") (pin "P$3") (pinfunction "P$3_P$3") (pintype "bidirectional"))
      (node (ref "J5") (pin "P$3") (pinfunction "P$3_P$3") (pintype "bidirectional"))
      (node (ref "J6") (pin "P$3") (pinfunction "P$3_P$3") (pintype "bidirectional"))
      (node (ref "U12") (pin "3") (pinfunction "C(3)_3") (pintype "input"))
      (node (ref "U16") (pin "3") (pinfunction "C(3)_3") (pintype "input"))
      (node (ref "U32") (pin "3") (pinfunction "C(3)_3") (pintype "input"))
      (node (ref "U7") (pin "3") (pinfunction "C(3)_3") (pintype "input"))
    )
    (net (code "19") (name "F3_OUT") (class "Default")
      (node (ref "J13") (pin "P$4") (pinfunction "P$4_P$4") (pintype "bidirectional"))
      (node (ref "J14") (pin "P$4") (pinfunction "P$4_P$4") (pintype "bidirectional"))
      (node (ref "J5") (pin "P$4") (pinfunction "P$4_P$4") (pintype "bidirectional"))
      (node (ref "J6") (pin "P$4") (pinfunction "P$4_P$4") (pintype "bidirectional"))
      (node (ref "U10") (pin "3") (pinfunction "C(3)_3") (pintype "input"))
      (node (ref "U15") (pin "3") (pinfunction "C(3)_3") (pintype "input"))
      (node (ref "U19") (pin "3") (pinfunction "C(3)_3") (pintype "input"))
      (node (ref "U35") (pin "3") (pinfunction "C(3)_3") (pintype "input"))
    )
    (net (code "20") (name "GND") (class "Default")
      (node (ref "C10") (pin "P$1") (pinfunction "1_P$1") (pintype "passive"))
      (node (ref "C11") (pin "P$2") (pinfunction "2_P$2") (pintype "passive"))
      (node (ref "C13") (pin "P$1") (pinfunction "1_P$1") (pintype "passive"))
      (node (ref "C14") (pin "P$1") (pinfunction "1_P$1") (pintype "passive"))
      (node (ref "C15") (pin "2") (pinfunction "2_2") (pintype "passive"))
      (node (ref "C16") (pin "P$2") (pinfunction "2_P$2") (pintype "passive"))
      (node (ref "C30") (pin "P$1") (pinfunction "1_P$1") (pintype "passive"))
      (node (ref "C31") (pin "P$2") (pinfunction "2_P$2") (pintype "passive"))
      (node (ref "C32") (pin "P$2") (pinfunction "2_P$2") (pintype "passive"))
      (node (ref "C33") (pin "P$2") (pinfunction "2_P$2") (pintype "passive"))
      (node (ref "C34") (pin "P$2") (pinfunction "2_P$2") (pintype "passive"))
      (node (ref "C35") (pin "P$2") (pinfunction "2_P$2") (pintype "passive"))
      (node (ref "C36") (pin "P$1") (pinfunction "1_P$1") (pintype "passive"))
      (node (ref "C37") (pin "P$1") (pinfunction "1_P$1") (pintype "passive"))
      (node (ref "C38") (pin "P$2") (pinfunction "2_P$2") (pintype "passive"))
      (node (ref "C39") (pin "P$2") (pinfunction "2_P$2") (pintype "passive"))
      (node (ref "C40") (pin "P$2") (pinfunction "2_P$2") (pintype "passive"))
      (node (ref "C41") (pin "P$2") (pinfunction "2_P$2") (pintype "passive"))
      (node (ref "C42") (pin "P$2") (pinfunction "2_P$2") (pintype "passive"))
      (node (ref "C43") (pin "2") (pinfunction "2_2") (pintype "passive"))
      (node (ref "C44") (pin "P$2") (pinfunction "2_P$2") (pintype "passive"))
      (node (ref "C45") (pin "P$2") (pinfunction "2_P$2") (pintype "passive"))
      (node (ref "C46") (pin "P$2") (pinfunction "2_P$2") (pintype "passive"))
      (node (ref "C47") (pin "P$2") (pinfunction "2_P$2") (pintype "passive"))
      (node (ref "C48") (pin "2") (pinfunction "2_2") (pintype "passive"))
      (node (ref "C49") (pin "P$2") (pinfunction "2_P$2") (pintype "passive"))
      (node (ref "C5") (pin "P$2") (pinfunction "2_P$2") (pintype "passive"))
      (node (ref "C50") (pin "P$2") (pinfunction "2_P$2") (pintype "passive"))
      (node (ref "C51") (pin "P$2") (pinfunction "2_P$2") (pintype "passive"))
      (node (ref "C52") (pin "P$2") (pinfunction "2_P$2") (pintype "passive"))
      (node (ref "C53") (pin "P$2") (pinfunction "2_P$2") (pintype "passive"))
      (node (ref "C54") (pin "P$1") (pinfunction "1_P$1") (pintype "passive"))
      (node (ref "C55") (pin "P$1") (pinfunction "1_P$1") (pintype "passive"))
      (node (ref "C56") (pin "P$1") (pinfunction "1_P$1") (pintype "passive"))
      (node (ref "C57") (pin "P$2") (pinfunction "2_P$2") (pintype "passive"))
      (node (ref "C58") (pin "P$2") (pinfunction "2_P$2") (pintype "passive"))
      (node (ref "C59") (pin "P$2") (pinfunction "2_P$2") (pintype "passive"))
      (node (ref "C60") (pin "P$2") (pinfunction "2_P$2") (pintype "passive"))
      (node (ref "C61") (pin "P$1") (pinfunction "1_P$1") (pintype "passive"))
      (node (ref "C8") (pin "P$2") (pinfunction "2_P$2") (pintype "passive"))
      (node (ref "J1") (pin "1") (pinfunction "1_1") (pintype "passive"))
      (node (ref "J1") (pin "2") (pinfunction "2_2") (pintype "passive"))
      (node (ref "J11") (pin "10") (pinfunction "10_10") (pintype "passive"))
      (node (ref "J11") (pin "6") (pinfunction "6_6") (pintype "passive"))
      (node (ref "J11") (pin "8") (pinfunction "8_8") (pintype "passive"))
      (node (ref "J16") (pin "10") (pinfunction "10_10") (pintype "passive"))
      (node (ref "J16") (pin "2") (pinfunction "2_2") (pintype "passive"))
      (node (ref "J16") (pin "4") (pinfunction "4_4") (pintype "passive"))
      (node (ref "J16") (pin "6") (pinfunction "6_6") (pintype "passive"))
      (node (ref "J16") (pin "8") (pinfunction "8_8") (pintype "passive"))
      (node (ref "J2") (pin "P$5") (pinfunction "GND_P$5") (pintype "bidirectional"))
      (node (ref "J3") (pin "GND") (pinfunction "GND_GND") (pintype "power_in"))
      (node (ref "J4") (pin "10") (pinfunction "GLO_10") (pintype "bidirectional"))
      (node (ref "J4") (pin "8") (pinfunction "P8_8") (pintype "bidirectional"))
      (node (ref "J9") (pin "6") (pinfunction "SUPPLY_VOLTAGE_GROUND_6") (pintype "power_in"))
      (node (ref "LED3") (pin "C") (pinfunction "C_C") (pintype "passive"))
      (node (ref "R16") (pin "P$1") (pinfunction "1_P$1") (pintype "passive"))
      (node (ref "R17") (pin "P$1") (pinfunction "1_P$1") (pintype "passive"))
      (node (ref "R19") (pin "P$1") (pinfunction "1_P$1") (pintype "passive"))
      (node (ref "R25") (pin "P$1") (pinfunction "1_P$1") (pintype "passive"))
      (node (ref "R7") (pin "P$1") (pinfunction "1_P$1") (pintype "passive"))
      (node (ref "U$1") (pin "P$2") (pinfunction "2_P$2") (pintype "passive"))
      (node (ref "U$10") (pin "P$2") (pinfunction "2_P$2") (pintype "passive"))
      (node (ref "U$12") (pin "P$2") (pinfunction "2_P$2") (pintype "passive"))
      (node (ref "U$13") (pin "P$2") (pinfunction "2_P$2") (pintype "passive"))
      (node (ref "U$14") (pin "P$2") (pinfunction "2_P$2") (pintype "passive"))
      (node (ref "U$15") (pin "P$2") (pinfunction "2_P$2") (pintype "passive"))
      (node (ref "U$16") (pin "P$2") (pinfunction "2_P$2") (pintype "passive"))
      (node (ref "U$17") (pin "P$2") (pinfunction "2_P$2") (pintype "passive"))
      (node (ref "U$18") (pin "P$2") (pinfunction "2_P$2") (pintype "passive"))
      (node (ref "U$3") (pin "2") (pinfunction "2_2") (pintype "bidirectional"))
      (node (ref "U$3") (pin "4") (pinfunction "4_4") (pintype "bidirectional"))
      (node (ref "U$32") (pin "P$2") (pinfunction "2_P$2") (pintype "passive"))
      (node (ref "U$33") (pin "P$2") (pinfunction "2_P$2") (pintype "passive"))
      (node (ref "U$34") (pin "P$2") (pinfunction "2_P$2") (pintype "passive"))
      (node (ref "U$35") (pin "P$2") (pinfunction "2_P$2") (pintype "passive"))
      (node (ref "U$4") (pin "P$2") (pinfunction "2_P$2") (pintype "passive"))
      (node (ref "U$5") (pin "P$2") (pinfunction "2_P$2") (pintype "passive"))
      (node (ref "U$6") (pin "P$2") (pinfunction "2_P$2") (pintype "passive"))
      (node (ref "U$8") (pin "P$2") (pinfunction "2_P$2") (pintype "passive"))
      (node (ref "U10") (pin "2") (pinfunction "E(1)_2") (pintype "output"))
      (node (ref "U12") (pin "2") (pinfunction "E(1)_2") (pintype "output"))
      (node (ref "U13") (pin "2") (pinfunction "E(1)_2") (pintype "output"))
      (node (ref "U14") (pin "2") (pinfunction "E(1)_2") (pintype "output"))
      (node (ref "U15") (pin "2") (pinfunction "E(1)_2") (pintype "output"))
      (node (ref "U16") (pin "2") (pinfunction "E(1)_2") (pintype "output"))
      (node (ref "U17") (pin "2") (pinfunction "E(1)_2") (pintype "output"))
      (node (ref "U18") (pin "2") (pinfunction "E(1)_2") (pintype "output"))
      (node (ref "U19") (pin "2") (pinfunction "E(1)_2") (pintype "output"))
      (node (ref "U2") (pin "2") (pinfunction "GND_2") (pintype "input"))
      (node (ref "U3") (pin "22") (pinfunction "GND_22") (pintype "power_in"))
      (node (ref "U3") (pin "25") (pinfunction "25_25") (pintype "passive"))
      (node (ref "U32") (pin "2") (pinfunction "E(1)_2") (pintype "output"))
      (node (ref "U33") (pin "2") (pinfunction "E(1)_2") (pintype "output"))
      (node (ref "U34") (pin "2") (pinfunction "E(1)_2") (pintype "output"))
      (node (ref "U35") (pin "2") (pinfunction "E(1)_2") (pintype "output"))
      (node (ref "U4") (pin "111") (pinfunction "VSS(IO)5_111") (pintype "bidirectional"))
      (node (ref "U4") (pin "124") (pinfunction "VSS(IO)6_124") (pintype "bidirectional"))
      (node (ref "U4") (pin "139") (pinfunction "VSS(IO)7_139") (pintype "bidirectional"))
      (node (ref "U4") (pin "150") (pinfunction "VSS(IO)8_150") (pintype "bidirectional"))
      (node (ref "U4") (pin "156") (pinfunction "AVSS0_156") (pintype "bidirectional"))
      (node (ref "U4") (pin "170") (pinfunction "VSS(IO)9_170") (pintype "bidirectional"))
      (node (ref "U4") (pin "22") (pinfunction "VSS1_22") (pintype "bidirectional"))
      (node (ref "U4") (pin "28") (pinfunction "AVSS_USBHS_28") (pintype "bidirectional"))
      (node (ref "U4") (pin "29") (pinfunction "PVSS_USBHS_29") (pintype "bidirectional"))
      (node (ref "U4") (pin "30") (pinfunction "VSS2_USBHS_30") (pintype "bidirectional"))
      (node (ref "U4") (pin "33") (pinfunction "VSS1_USBHS_33") (pintype "bidirectional"))
      (node (ref "U4") (pin "35") (pinfunction "VSSIO_35") (pintype "bidirectional"))
      (node (ref "U4") (pin "45") (pinfunction "VSS_USB_45") (pintype "bidirectional"))
      (node (ref "U4") (pin "60") (pinfunction "VSS(IO)2_60") (pintype "bidirectional"))
      (node (ref "U4") (pin "63") (pinfunction "VSS(IO/DCDC)_63") (pintype "bidirectional"))
      (node (ref "U4") (pin "66") (pinfunction "VCC_DCDC(IO/DCDC)_66") (pintype "bidirectional"))
      (node (ref "U4") (pin "83") (pinfunction "VSS(IO)3_83") (pintype "bidirectional"))
      (node (ref "U4") (pin "98") (pinfunction "VSS(IO)4_98") (pintype "bidirectional"))
      (node (ref "U7") (pin "2") (pinfunction "E(1)_2") (pintype "output"))
      (node (ref "U8") (pin "2") (pinfunction "E(1)_2") (pintype "output"))
      (node (ref "U9") (pin "2") (pinfunction "E(1)_2") (pintype "output"))
      (node (ref "X4") (pin "2") (pinfunction "2_2") (pintype "bidirectional"))
      (node (ref "X4") (pin "4") (pinfunction "4_4") (pintype "bidirectional"))
    )
    (net (code "21") (name "GNDE") (class "Default")
      (node (ref "J1") (pin "10") (pinfunction "10_10") (pintype "passive"))
      (node (ref "J1") (pin "9") (pinfunction "9_9") (pintype "passive"))
      (node (ref "J2") (pin "P$6") (pinfunction "SHIELD1_P$6") (pintype "bidirectional"))
      (node (ref "J2") (pin "P$7") (pinfunction "SHIELD2_P$7") (pintype "bidirectional"))
      (node (ref "J2") (pin "P$8") (pinfunction "SHIELD3_P$8") (pintype "bidirectional"))
      (node (ref "J2") (pin "P$9") (pinfunction "SHIELD4_P$9") (pintype "bidirectional"))
      (node (ref "J3") (pin "SHLD1") (pinfunction "SHIELD_1_SHLD1") (pintype "bidirectional"))
      (node (ref "J3") (pin "SHLD2") (pinfunction "SHIELD_2_SHLD2") (pintype "bidirectional"))
      (node (ref "J4") (pin "13") (pinfunction "GNDE0_13") (pintype "bidirectional"))
      (node (ref "J4") (pin "14") (pinfunction "GNDE1_14") (pintype "bidirectional"))
      (node (ref "J9") (pin "S1") (pinfunction "SHIELD_S1") (pintype "passive"))
      (node (ref "J9") (pin "S2") (pinfunction "SHIELD_S2") (pintype "passive"))
      (node (ref "J9") (pin "S3") (pinfunction "SHIELD_S3") (pintype "passive"))
      (node (ref "J9") (pin "S4") (pinfunction "SHIELD_S4") (pintype "passive"))
    )
    (net (code "22") (name "GP4") (class "Default")
      (node (ref "U4") (pin "49") (pinfunction "P2_7_49") (pintype "bidirectional"))
    )
    (net (code "23") (name "GP21") (class "Default")
      (node (ref "U4") (pin "73") (pinfunction "P9_5_73") (pintype "bidirectional"))
    )
    (net (code "24") (name "ID") (class "Default")
      (node (ref "J2") (pin "P$4") (pinfunction "ID_P$4") (pintype "bidirectional"))
    )
    (net (code "25") (name "IIC_0_SCL") (class "Default")
      (node (ref "J7") (pin "10") (pinfunction "10_10") (pintype "passive"))
      (node (ref "R11") (pin "P$2") (pinfunction "2_P$2") (pintype "passive"))
      (node (ref "U4") (pin "1") (pinfunction "P4_0_1") (pintype "bidirectional"))
    )
    (net (code "26") (name "IIC_0_SDA") (class "Default")
      (node (ref "J7") (pin "9") (pinfunction "9_9") (pintype "passive"))
      (node (ref "R14") (pin "P$2") (pinfunction "2_P$2") (pintype "passive"))
      (node (ref "U4") (pin "2") (pinfunction "P4_1_2") (pintype "bidirectional"))
    )
    (net (code "27") (name "IIC_1_SCL") (class "Default")
      (node (ref "J10") (pin "P$5") (pinfunction "P$5_P$5") (pintype "bidirectional"))
      (node (ref "R20") (pin "P$2") (pinfunction "2_P$2") (pintype "passive"))
      (node (ref "U4") (pin "132") (pinfunction "P1_0_132") (pintype "bidirectional"))
    )
    (net (code "28") (name "IIC_1_SDA") (class "Default")
      (node (ref "J10") (pin "P$6") (pinfunction "P$6_P$6") (pintype "bidirectional"))
      (node (ref "R21") (pin "P$2") (pinfunction "2_P$2") (pintype "passive"))
      (node (ref "U4") (pin "131") (pinfunction "P1_1_131") (pintype "bidirectional"))
    )
    (net (code "29") (name "INT_AI_LS_0") (class "Default")
      (node (ref "J15") (pin "P$1") (pinfunction "P$1_P$1") (pintype "bidirectional"))
      (node (ref "U4") (pin "3") (pinfunction "P4_2_3") (pintype "bidirectional"))
    )
    (net (code "30") (name "INT_AI_LS_1") (class "Default")
      (node (ref "J15") (pin "P$2") (pinfunction "P$2_P$2") (pintype "bidirectional"))
      (node (ref "U4") (pin "43") (pinfunction "P4_8_43") (pintype "bidirectional"))
    )
    (net (code "31") (name "INT_AI_LS_2") (class "Default")
      (node (ref "J15") (pin "P$3") (pinfunction "P$3_P$3") (pintype "bidirectional"))
      (node (ref "U4") (pin "53") (pinfunction "P2_3_53") (pintype "bidirectional"))
    )
    (net (code "32") (name "INT_AI_LS_3") (class "Default")
      (node (ref "J15") (pin "P$4") (pinfunction "P$4_P$4") (pintype "bidirectional"))
      (node (ref "U4") (pin "54") (pinfunction "P2_2_54") (pintype "bidirectional"))
    )
    (net (code "33") (name "INT_MI_01") (class "Default")
      (node (ref "J10") (pin "P$39") (pinfunction "P$39_P$39") (pintype "bidirectional"))
      (node (ref "U4") (pin "87") (pinfunction "P3_1_87") (pintype "bidirectional"))
    )
    (net (code "34") (name "INT_MI_02") (class "Default")
      (node (ref "J10") (pin "P$40") (pinfunction "P$40_P$40") (pintype "bidirectional"))
      (node (ref "U4") (pin "86") (pinfunction "P3_2_86") (pintype "bidirectional"))
    )
    (net (code "35") (name "INT_MI_03") (class "Default")
      (node (ref "J10") (pin "P$9") (pinfunction "P$9_P$9") (pintype "bidirectional"))
      (node (ref "U4") (pin "128") (pinfunction "P1_4_128") (pintype "bidirectional"))
    )
    (net (code "36") (name "INT_MI_04") (class "Default")
      (node (ref "J10") (pin "P$10") (pinfunction "P$10_P$10") (pintype "bidirectional"))
      (node (ref "U4") (pin "127") (pinfunction "P1_5_127") (pintype "bidirectional"))
    )
    (net (code "37") (name "INT_MI_05") (class "Default")
      (node (ref "J10") (pin "P$1") (pinfunction "P$1_P$1") (pintype "bidirectional"))
    )
    (net (code "38") (name "LED1{slash}SPEED") (class "Default")
      (node (ref "J4") (pin "11") (pinfunction "YLO_11") (pintype "bidirectional"))
      (node (ref "U3") (pin "23") (pinfunction "LED0/ANEN_SPEED_23") (pintype "bidirectional"))
    )
    (net (code "39") (name "M0_DIR") (class "Default")
      (node (ref "RXS4") (pin "P$1") (pinfunction "1_P$1") (pintype "passive"))
      (node (ref "U4") (pin "39") (pinfunction "P4_12_39") (pintype "bidirectional"))
    )
    (net (code "40") (name "M0_STEP") (class "Default")
      (node (ref "RXS2") (pin "P$1") (pinfunction "1_P$1") (pintype "passive"))
      (node (ref "U4") (pin "16") (pinfunction "PB_0_16") (pintype "bidirectional"))
    )
    (net (code "41") (name "M1_DIR") (class "Default")
      (node (ref "RYS7") (pin "P$1") (pinfunction "1_P$1") (pintype "passive"))
      (node (ref "U4") (pin "40") (pinfunction "P4_11_40") (pintype "bidirectional"))
    )
    (net (code "42") (name "M1_STEP") (class "Default")
      (node (ref "RYS3") (pin "P$1") (pinfunction "1_P$1") (pintype "passive"))
      (node (ref "U4") (pin "36") (pinfunction "P4_15_36") (pintype "bidirectional"))
    )
    (net (code "43") (name "M2_DIR") (class "Default")
      (node (ref "RZS4") (pin "P$1") (pinfunction "1_P$1") (pintype "passive"))
      (node (ref "U4") (pin "41") (pinfunction "P4_10_41") (pintype "bidirectional"))
    )
    (net (code "44") (name "M2_STEP") (class "Default")
      (node (ref "RZS2") (pin "P$1") (pinfunction "1_P$1") (pintype "passive"))
      (node (ref "U4") (pin "37") (pinfunction "P4_14_37") (pintype "bidirectional"))
    )
    (net (code "45") (name "M3_DIR") (class "Default")
      (node (ref "RYS8") (pin "P$1") (pinfunction "1_P$1") (pintype "passive"))
      (node (ref "U4") (pin "42") (pinfunction "P4_9_42") (pintype "bidirectional"))
    )
    (net (code "46") (name "M3_STEP") (class "Default")
      (node (ref "RYS4") (pin "P$1") (pinfunction "1_P$1") (pintype "passive"))
      (node (ref "U4") (pin "38") (pinfunction "P4_13_38") (pintype "bidirectional"))
    )
    (net (code "47") (name "NC") (class "Default")
      (node (ref "J4") (pin "7") (pinfunction "P7_7") (pintype "bidirectional"))
    )
    (net (code "48") (name "Net-(C16-1)") (class "Default")
      (node (ref "C16") (pin "P$1") (pinfunction "1_P$1") (pintype "passive"))
      (node (ref "J2") (pin "P$1") (pinfunction "VBUS_P$1") (pintype "bidirectional"))
      (node (ref "R4") (pin "P$2") (pinfunction "2_P$2") (pintype "passive"))
      (node (ref "R7") (pin "P$2") (pinfunction "2_P$2") (pintype "passive"))
    )
    (net (code "49") (name "Net-(C31-1)") (class "Default")
      (node (ref "C31") (pin "P$1") (pinfunction "1_P$1") (pintype "passive"))
      (node (ref "U4") (pin "62") (pinfunction "VCL1_62") (pintype "bidirectional"))
    )
    (net (code "50") (name "Net-(C37-2)") (class "Default")
      (node (ref "C37") (pin "P$2") (pinfunction "2_P$2") (pintype "passive"))
      (node (ref "U4") (pin "148") (pinfunction "VCL2_148") (pintype "bidirectional"))
    )
    (net (code "51") (name "Net-(C38-1)") (class "Default")
      (node (ref "C38") (pin "P$1") (pinfunction "1_P$1") (pintype "passive"))
      (node (ref "U4") (pin "19") (pinfunction "VCLO_19") (pintype "bidirectional"))
    )
    (net (code "52") (name "Net-(C44-1)") (class "Default")
      (node (ref "C43") (pin "1") (pinfunction "1_1") (pintype "passive"))
      (node (ref "C44") (pin "P$1") (pinfunction "1_P$1") (pintype "passive"))
      (node (ref "FB2/2") (pin "2") (pinfunction "P$2_2") (pintype "bidirectional"))
      (node (ref "U3") (pin "2") (pinfunction "VDDA_3.3_2") (pintype "power_in"))
    )
    (net (code "53") (name "Net-(J2-D+)") (class "Default")
      (node (ref "J2") (pin "P$3") (pinfunction "D+_P$3") (pintype "bidirectional"))
      (node (ref "R6") (pin "P$2") (pinfunction "2_P$2") (pintype "passive"))
    )
    (net (code "54") (name "Net-(J2-D-)") (class "Default")
      (node (ref "J2") (pin "P$2") (pinfunction "D-_P$2") (pintype "bidirectional"))
      (node (ref "R5") (pin "P$2") (pinfunction "2_P$2") (pintype "passive"))
    )
    (net (code "55") (name "Net-(R13-1)") (class "Default")
      (node (ref "LED3") (pin "A") (pinfunction "A_A") (pintype "passive"))
      (node (ref "R13") (pin "P$1") (pinfunction "1_P$1") (pintype "passive"))
    )
    (net (code "56") (name "Net-(R16-2)") (class "Default")
      (node (ref "R16") (pin "P$2") (pinfunction "2_P$2") (pintype "passive"))
      (node (ref "U4") (pin "65") (pinfunction "VLO2(DCDC)_65") (pintype "bidirectional"))
    )
    (net (code "57") (name "Net-(R17-2)") (class "Default")
      (node (ref "R17") (pin "P$2") (pinfunction "2_P$2") (pintype "passive"))
      (node (ref "U4") (pin "64") (pinfunction "VLO1(DCDC)_64") (pintype "bidirectional"))
    )
    (net (code "58") (name "Net-(R19-2)") (class "Default")
      (node (ref "R19") (pin "P$2") (pinfunction "2_P$2") (pintype "passive"))
      (node (ref "U4") (pin "27") (pinfunction "USBHS_RREF_27") (pintype "bidirectional"))
    )
    (net (code "59") (name "Net-(RXS2-2)") (class "Default")
      (node (ref "RXS2") (pin "P$2") (pinfunction "2_P$2") (pintype "passive"))
      (node (ref "U$5") (pin "P$1") (pinfunction "1_P$1") (pintype "passive"))
      (node (ref "U8") (pin "1") (pinfunction "B(2)_1") (pintype "input"))
    )
    (net (code "60") (name "Net-(RXS3-2)") (class "Default")
      (node (ref "RXS3") (pin "P$2") (pinfunction "2_P$2") (pintype "passive"))
      (node (ref "U$12") (pin "P$1") (pinfunction "1_P$1") (pintype "passive"))
      (node (ref "U13") (pin "1") (pinfunction "B(2)_1") (pintype "input"))
    )
    (net (code "61") (name "Net-(RXS4-2)") (class "Default")
      (node (ref "RXS4") (pin "P$2") (pinfunction "2_P$2") (pintype "passive"))
      (node (ref "U$16") (pin "P$1") (pinfunction "1_P$1") (pintype "passive"))
      (node (ref "U17") (pin "1") (pinfunction "B(2)_1") (pintype "input"))
    )
    (net (code "62") (name "Net-(RXS8-2)") (class "Default")
      (node (ref "RXS8") (pin "P$2") (pinfunction "2_P$2") (pintype "passive"))
      (node (ref "U$33") (pin "P$1") (pinfunction "1_P$1") (pintype "passive"))
      (node (ref "U33") (pin "1") (pinfunction "B(2)_1") (pintype "input"))
    )
    (net (code "63") (name "Net-(RYS3-2)") (class "Default")
      (node (ref "RYS3") (pin "P$2") (pinfunction "2_P$2") (pintype "passive"))
      (node (ref "U$6") (pin "P$1") (pinfunction "1_P$1") (pintype "passive"))
      (node (ref "U9") (pin "1") (pinfunction "B(2)_1") (pintype "input"))
    )
    (net (code "64") (name "Net-(RYS4-2)") (class "Default")
      (node (ref "RYS4") (pin "P$2") (pinfunction "2_P$2") (pintype "passive"))
      (node (ref "U$8") (pin "P$1") (pinfunction "1_P$1") (pintype "passive"))
      (node (ref "U10") (pin "1") (pinfunction "B(2)_1") (pintype "input"))
    )
    (net (code "65") (name "Net-(RYS5-2)") (class "Default")
      (node (ref "RYS5") (pin "P$2") (pinfunction "2_P$2") (pintype "passive"))
      (node (ref "U$13") (pin "P$1") (pinfunction "1_P$1") (pintype "passive"))
      (node (ref "U14") (pin "1") (pinfunction "B(2)_1") (pintype "input"))
    )
    (net (code "66") (name "Net-(RYS6-2)") (class "Default")
      (node (ref "RYS6") (pin "P$2") (pinfunction "2_P$2") (pintype "passive"))
      (node (ref "U$14") (pin "P$1") (pinfunction "1_P$1") (pintype "passive"))
      (node (ref "U15") (pin "1") (pinfunction "B(2)_1") (pintype "input"))
    )
    (net (code "67") (name "Net-(RYS7-2)") (class "Default")
      (node (ref "RYS7") (pin "P$2") (pinfunction "2_P$2") (pintype "passive"))
      (node (ref "U$17") (pin "P$1") (pinfunction "1_P$1") (pintype "passive"))
      (node (ref "U18") (pin "1") (pinfunction "B(2)_1") (pintype "input"))
    )
    (net (code "68") (name "Net-(RYS8-2)") (class "Default")
      (node (ref "RYS8") (pin "P$2") (pinfunction "2_P$2") (pintype "passive"))
      (node (ref "U$18") (pin "P$1") (pinfunction "1_P$1") (pintype "passive"))
      (node (ref "U19") (pin "1") (pinfunction "B(2)_1") (pintype "input"))
    )
    (net (code "69") (name "Net-(RYS15-2)") (class "Default")
      (node (ref "RYS15") (pin "P$2") (pinfunction "2_P$2") (pintype "passive"))
      (node (ref "U$34") (pin "P$1") (pinfunction "1_P$1") (pintype "passive"))
      (node (ref "U34") (pin "1") (pinfunction "B(2)_1") (pintype "input"))
    )
    (net (code "70") (name "Net-(RYS16-2)") (class "Default")
      (node (ref "RYS16") (pin "P$2") (pinfunction "2_P$2") (pintype "passive"))
      (node (ref "U$35") (pin "P$1") (pinfunction "1_P$1") (pintype "passive"))
      (node (ref "U35") (pin "1") (pinfunction "B(2)_1") (pintype "input"))
    )
    (net (code "71") (name "Net-(RZS2-2)") (class "Default")
      (node (ref "RZS2") (pin "P$2") (pinfunction "2_P$2") (pintype "passive"))
      (node (ref "U$1") (pin "P$1") (pinfunction "1_P$1") (pintype "passive"))
      (node (ref "U7") (pin "1") (pinfunction "B(2)_1") (pintype "input"))
    )
    (net (code "72") (name "Net-(RZS3-2)") (class "Default")
      (node (ref "RZS3") (pin "P$2") (pinfunction "2_P$2") (pintype "passive"))
      (node (ref "U$10") (pin "P$1") (pinfunction "1_P$1") (pintype "passive"))
      (node (ref "U12") (pin "1") (pinfunction "B(2)_1") (pintype "input"))
    )
    (net (code "73") (name "Net-(RZS4-2)") (class "Default")
      (node (ref "RZS4") (pin "P$2") (pinfunction "2_P$2") (pintype "passive"))
      (node (ref "U$15") (pin "P$1") (pinfunction "1_P$1") (pintype "passive"))
      (node (ref "U16") (pin "1") (pinfunction "B(2)_1") (pintype "input"))
    )
    (net (code "74") (name "Net-(RZS8-2)") (class "Default")
      (node (ref "RZS8") (pin "P$2") (pinfunction "2_P$2") (pintype "passive"))
      (node (ref "U$32") (pin "P$1") (pinfunction "1_P$1") (pintype "passive"))
      (node (ref "U32") (pin "1") (pinfunction "B(2)_1") (pintype "input"))
    )
    (net (code "75") (name "P0_00") (class "Default")
      (node (ref "J7") (pin "3") (pinfunction "3_3") (pintype "passive"))
      (node (ref "U4") (pin "169") (pinfunction "P0_0/AN0\\00_169") (pintype "bidirectional"))
    )
    (net (code "76") (name "P0_01") (class "Default")
      (node (ref "J7") (pin "4") (pinfunction "4_4") (pintype "passive"))
      (node (ref "U4") (pin "168") (pinfunction "P0_1/AN001_168") (pintype "bidirectional"))
    )
    (net (code "77") (name "P0_02") (class "Default")
      (node (ref "J7") (pin "1") (pinfunction "1_1") (pintype "passive"))
      (node (ref "U4") (pin "167") (pinfunction "P0_2/AN002_167") (pintype "bidirectional"))
    )
    (net (code "78") (name "P0_03") (class "Default")
      (node (ref "J7") (pin "2") (pinfunction "2_2") (pintype "passive"))
      (node (ref "U4") (pin "166") (pinfunction "P0_3/PGAVSS000_166") (pintype "bidirectional"))
    )
    (net (code "79") (name "P0_04") (class "Default")
      (node (ref "J8") (pin "9") (pinfunction "9_9") (pintype "passive"))
      (node (ref "U4") (pin "165") (pinfunction "P0_4/AN100_165") (pintype "bidirectional"))
    )
    (net (code "80") (name "P0_05") (class "Default")
      (node (ref "J8") (pin "10") (pinfunction "10_10") (pintype "passive"))
      (node (ref "U4") (pin "164") (pinfunction "P0_5/AN101_164") (pintype "bidirectional"))
    )
    (net (code "81") (name "P0_06") (class "Default")
      (node (ref "J8") (pin "7") (pinfunction "7_7") (pintype "passive"))
      (node (ref "U4") (pin "163") (pinfunction "P0_6/AN102_163") (pintype "bidirectional"))
    )
    (net (code "82") (name "P0_07") (class "Default")
      (node (ref "J8") (pin "8") (pinfunction "8_8") (pintype "passive"))
      (node (ref "U4") (pin "162") (pinfunction "P0_7/PGVSS100_162") (pintype "bidirectional"))
    )
    (net (code "83") (name "P0_08") (class "Default")
      (node (ref "J8") (pin "5") (pinfunction "5_5") (pintype "passive"))
      (node (ref "U4") (pin "161") (pinfunction "P0_8/AN003_161") (pintype "bidirectional"))
    )
    (net (code "84") (name "P0_09") (class "Default")
      (node (ref "J8") (pin "6") (pinfunction "6_6") (pintype "passive"))
      (node (ref "U4") (pin "160") (pinfunction "P0_9/AN004_160") (pintype "bidirectional"))
    )
    (net (code "85") (name "P0_14") (class "Default")
      (node (ref "J8") (pin "3") (pinfunction "3_3") (pintype "passive"))
      (node (ref "U4") (pin "152") (pinfunction "P0_14/DA0/AN005/AN105_152") (pintype "bidirectional"))
    )
    (net (code "86") (name "P0_15") (class "Default")
      (node (ref "J8") (pin "4") (pinfunction "4_4") (pintype "passive"))
      (node (ref "U4") (pin "151") (pinfunction "P0_15/DA1/AN006/AN106_151") (pintype "bidirectional"))
    )
    (net (code "87") (name "P1_02") (class "Default")
      (node (ref "J10") (pin "P$7") (pinfunction "P$7_P$7") (pintype "bidirectional"))
      (node (ref "U4") (pin "130") (pinfunction "P1_2_130") (pintype "bidirectional"))
    )
    (net (code "88") (name "P1_03") (class "Default")
      (node (ref "J10") (pin "P$8") (pinfunction "P$8_P$8") (pintype "bidirectional"))
      (node (ref "U4") (pin "129") (pinfunction "P1_3_129") (pintype "bidirectional"))
    )
    (net (code "89") (name "P1_06") (class "Default")
      (node (ref "J10") (pin "P$11") (pinfunction "P$11_P$11") (pintype "bidirectional"))
      (node (ref "U4") (pin "126") (pinfunction "P1_6_126") (pintype "bidirectional"))
    )
    (net (code "90") (name "P1_07") (class "Default")
      (node (ref "J10") (pin "P$12") (pinfunction "P$12_P$12") (pintype "bidirectional"))
      (node (ref "U4") (pin "125") (pinfunction "P1_7_125") (pintype "bidirectional"))
    )
    (net (code "91") (name "P1_11") (class "Default")
      (node (ref "J10") (pin "P$38") (pinfunction "P$38_P$38") (pintype "bidirectional"))
      (node (ref "U4") (pin "92") (pinfunction "P1_11_92") (pintype "bidirectional"))
    )
    (net (code "92") (name "P1_12") (class "Default")
      (node (ref "J10") (pin "P$37") (pinfunction "P$37_P$37") (pintype "bidirectional"))
      (node (ref "U4") (pin "93") (pinfunction "P1_12_93") (pintype "bidirectional"))
    )
    (net (code "93") (name "P1_13") (class "Default")
      (node (ref "J10") (pin "P$36") (pinfunction "P$36_P$36") (pintype "bidirectional"))
      (node (ref "U4") (pin "94") (pinfunction "P1_13_94") (pintype "bidirectional"))
    )
    (net (code "94") (name "P1_14") (class "Default")
      (node (ref "J10") (pin "P$35") (pinfunction "P$35_P$35") (pintype "bidirectional"))
      (node (ref "U4") (pin "95") (pinfunction "P1_14_95") (pintype "bidirectional"))
    )
    (net (code "95") (name "P1_15") (class "Default")
      (node (ref "J10") (pin "P$34") (pinfunction "P$34_P$34") (pintype "bidirectional"))
      (node (ref "U4") (pin "96") (pinfunction "P1_15_96") (pintype "bidirectional"))
    )
    (net (code "96") (name "P2_00") (class "Default")
      (node (ref "J16") (pin "3") (pinfunction "3_3") (pintype "passive"))
      (node (ref "R3") (pin "P$2") (pinfunction "2_P$2") (pintype "passive"))
      (node (ref "U4") (pin "69") (pinfunction "P2_0(INPUT_ONLY)_69") (pintype "bidirectional"))
    )
    (net (code "97") (name "P2_01") (class "Default")
      (node (ref "J16") (pin "1") (pinfunction "1_1") (pintype "passive"))
      (node (ref "R2") (pin "P$2") (pinfunction "2_P$2") (pintype "passive"))
      (node (ref "U4") (pin "68") (pinfunction "P2_1/MD_68") (pintype "bidirectional"))
    )
    (net (code "98") (name "P3_03") (class "Default")
      (node (ref "J12") (pin "1") (pinfunction "1_1") (pintype "passive"))
      (node (ref "U4") (pin "85") (pinfunction "P3_3_85") (pintype "bidirectional"))
    )
    (net (code "99") (name "P3_04") (class "Default")
      (node (ref "J12") (pin "2") (pinfunction "2_2") (pintype "passive"))
      (node (ref "U4") (pin "82") (pinfunction "P3_4_82") (pintype "bidirectional"))
    )
    (net (code "100") (name "P3_05") (class "Default")
      (node (ref "J12") (pin "3") (pinfunction "3_3") (pintype "passive"))
      (node (ref "U4") (pin "81") (pinfunction "P3_5_81") (pintype "bidirectional"))
    )
    (net (code "101") (name "P3_06") (class "Default")
      (node (ref "J12") (pin "4") (pinfunction "4_4") (pintype "passive"))
      (node (ref "U4") (pin "80") (pinfunction "P3_6_80") (pintype "bidirectional"))
    )
    (net (code "102") (name "P3_07") (class "Default")
      (node (ref "J12") (pin "5") (pinfunction "5_5") (pintype "passive"))
      (node (ref "U4") (pin "79") (pinfunction "P3_7_79") (pintype "bidirectional"))
    )
    (net (code "103") (name "P3_09") (class "Default")
      (node (ref "J12") (pin "6") (pinfunction "6_6") (pintype "passive"))
      (node (ref "U4") (pin "77") (pinfunction "P3_9_77") (pintype "bidirectional"))
    )
    (net (code "104") (name "P3_10") (class "Default")
      (node (ref "J12") (pin "7") (pinfunction "7_7") (pintype "passive"))
      (node (ref "U4") (pin "76") (pinfunction "P3_10_76") (pintype "bidirectional"))
    )
    (net (code "105") (name "P3_11") (class "Default")
      (node (ref "J12") (pin "8") (pinfunction "8_8") (pintype "passive"))
      (node (ref "U4") (pin "75") (pinfunction "P3_11_75") (pintype "bidirectional"))
    )
    (net (code "106") (name "P3_12") (class "Default")
      (node (ref "J12") (pin "9") (pinfunction "9_9") (pintype "passive"))
      (node (ref "U4") (pin "74") (pinfunction "P3_12_74") (pintype "bidirectional"))
    )
    (net (code "107") (name "P5_11") (class "Default")
      (node (ref "J7") (pin "7") (pinfunction "7_7") (pintype "passive"))
      (node (ref "U4") (pin "176") (pinfunction "P5_11_176") (pintype "bidirectional"))
    )
    (net (code "108") (name "P5_12") (class "Default")
      (node (ref "J7") (pin "8") (pinfunction "8_8") (pintype "passive"))
      (node (ref "U4") (pin "175") (pinfunction "P5_12_175") (pintype "bidirectional"))
    )
    (net (code "109") (name "P5_13") (class "Default")
      (node (ref "J7") (pin "5") (pinfunction "5_5") (pintype "passive"))
      (node (ref "U4") (pin "174") (pinfunction "P5_13_174") (pintype "bidirectional"))
    )
    (net (code "110") (name "P6_00") (class "Default")
      (node (ref "J10") (pin "P$13") (pinfunction "P$13_P$13") (pintype "bidirectional"))
      (node (ref "U4") (pin "122") (pinfunction "P6_0_122") (pintype "bidirectional"))
    )
    (net (code "111") (name "P6_01") (class "Default")
      (node (ref "J10") (pin "P$14") (pinfunction "P$14_P$14") (pintype "bidirectional"))
      (node (ref "U4") (pin "121") (pinfunction "P6_1_121") (pintype "bidirectional"))
    )
    (net (code "112") (name "P6_02") (class "Default")
      (node (ref "J10") (pin "P$15") (pinfunction "P$15_P$15") (pintype "bidirectional"))
      (node (ref "U4") (pin "120") (pinfunction "P6_2_120") (pintype "bidirectional"))
    )
    (net (code "113") (name "P6_03") (class "Default")
      (node (ref "J10") (pin "P$16") (pinfunction "P$16_P$16") (pintype "bidirectional"))
      (node (ref "U4") (pin "119") (pinfunction "P6_3_119") (pintype "bidirectional"))
    )
    (net (code "114") (name "P6_04") (class "Default")
      (node (ref "J10") (pin "P$17") (pinfunction "P$17_P$17") (pintype "bidirectional"))
      (node (ref "U4") (pin "118") (pinfunction "P6_4_118") (pintype "bidirectional"))
    )
    (net (code "115") (name "P6_05") (class "Default")
      (node (ref "J10") (pin "P$18") (pinfunction "P$18_P$18") (pintype "bidirectional"))
      (node (ref "U4") (pin "117") (pinfunction "P6_5_117") (pintype "bidirectional"))
    )
    (net (code "116") (name "P6_06") (class "Default")
      (node (ref "J10") (pin "P$19") (pinfunction "P$19_P$19") (pintype "bidirectional"))
      (node (ref "U4") (pin "116") (pinfunction "P6_6_116") (pintype "bidirectional"))
    )
    (net (code "117") (name "P6_07") (class "Default")
      (node (ref "J10") (pin "P$20") (pinfunction "P$20_P$20") (pintype "bidirectional"))
      (node (ref "U4") (pin "115") (pinfunction "P6_7_115") (pintype "bidirectional"))
    )
    (net (code "118") (name "P6_08") (class "Default")
      (node (ref "J10") (pin "P$33") (pinfunction "P$33_P$33") (pintype "bidirectional"))
      (node (ref "U4") (pin "99") (pinfunction "P6_8_99") (pintype "bidirectional"))
    )
    (net (code "119") (name "P6_09") (class "Default")
      (node (ref "J10") (pin "P$32") (pinfunction "P$32_P$32") (pintype "bidirectional"))
      (node (ref "U4") (pin "100") (pinfunction "P6_9_100") (pintype "bidirectional"))
    )
    (net (code "120") (name "P6_10") (class "Default")
      (node (ref "J10") (pin "P$31") (pinfunction "P$31_P$31") (pintype "bidirectional"))
      (node (ref "U4") (pin "101") (pinfunction "P6_10_101") (pintype "bidirectional"))
    )
    (net (code "121") (name "P6_11") (class "Default")
      (node (ref "J10") (pin "P$30") (pinfunction "P$30_P$30") (pintype "bidirectional"))
      (node (ref "U4") (pin "102") (pinfunction "P6_11_102") (pintype "bidirectional"))
    )
    (net (code "122") (name "P6_12") (class "Default")
      (node (ref "J10") (pin "P$29") (pinfunction "P$29_P$29") (pintype "bidirectional"))
      (node (ref "U4") (pin "103") (pinfunction "P6_12_103") (pintype "bidirectional"))
    )
    (net (code "123") (name "P6_13") (class "Default")
      (node (ref "J10") (pin "P$28") (pinfunction "P$28_P$28") (pintype "bidirectional"))
      (node (ref "U4") (pin "104") (pinfunction "P6_13_104") (pintype "bidirectional"))
    )
    (net (code "124") (name "P6_14") (class "Default")
      (node (ref "J10") (pin "P$27") (pinfunction "P$27_P$27") (pintype "bidirectional"))
      (node (ref "U4") (pin "105") (pinfunction "P6_14_105") (pintype "bidirectional"))
    )
    (net (code "125") (name "P6_15") (class "Default")
      (node (ref "J10") (pin "P$26") (pinfunction "P$26_P$26") (pintype "bidirectional"))
      (node (ref "U4") (pin "106") (pinfunction "P6_15_106") (pintype "bidirectional"))
    )
    (net (code "126") (name "P7_06") (class "Default")
      (node (ref "U4") (pin "14") (pinfunction "P7_6_14") (pintype "bidirectional"))
    )
    (net (code "127") (name "P7_07") (class "Default")
      (node (ref "U4") (pin "15") (pinfunction "P7_7_15") (pintype "bidirectional"))
    )
    (net (code "128") (name "P8_00") (class "Default")
      (node (ref "J10") (pin "P$4") (pinfunction "P$4_P$4") (pintype "bidirectional"))
      (node (ref "U4") (pin "133") (pinfunction "P8_0_133") (pintype "bidirectional"))
    )
    (net (code "129") (name "P8_01") (class "Default")
      (node (ref "J10") (pin "P$3") (pinfunction "P$3_P$3") (pintype "bidirectional"))
      (node (ref "U4") (pin "134") (pinfunction "P8_1_134") (pintype "bidirectional"))
    )
    (net (code "130") (name "P8_02") (class "Default")
      (node (ref "J10") (pin "P$2") (pinfunction "P$2_P$2") (pintype "bidirectional"))
      (node (ref "U4") (pin "135") (pinfunction "P8_2_135") (pintype "bidirectional"))
    )
    (net (code "131") (name "P8_03") (class "Default")
      (node (ref "J8") (pin "2") (pinfunction "2_2") (pintype "passive"))
      (node (ref "U4") (pin "136") (pinfunction "P8_3_136") (pintype "bidirectional"))
    )
    (net (code "132") (name "P8_04") (class "Default")
      (node (ref "J8") (pin "1") (pinfunction "1_1") (pintype "passive"))
      (node (ref "U4") (pin "137") (pinfunction "P8_4_137") (pintype "bidirectional"))
    )
    (net (code "133") (name "P8_05") (class "Default")
      (node (ref "J7") (pin "6") (pinfunction "6_6") (pintype "passive"))
      (node (ref "U4") (pin "173") (pinfunction "P8_5_173") (pintype "bidirectional"))
    )
    (net (code "134") (name "P9_05") (class "Default")
      (node (ref "J12") (pin "10") (pinfunction "10_10") (pintype "passive"))
    )
    (net (code "135") (name "P9_06") (class "Default")
      (node (ref "J16") (pin "9") (pinfunction "9_9") (pintype "passive"))
      (node (ref "R10") (pin "P$2") (pinfunction "2_P$2") (pintype "passive"))
      (node (ref "U4") (pin "72") (pinfunction "P9_6_72") (pintype "bidirectional"))
    )
    (net (code "136") (name "P9_07") (class "Default")
      (node (ref "J16") (pin "7") (pinfunction "7_7") (pintype "passive"))
      (node (ref "R9") (pin "P$2") (pinfunction "2_P$2") (pintype "passive"))
      (node (ref "U4") (pin "71") (pinfunction "P9_7_71") (pintype "bidirectional"))
    )
    (net (code "137") (name "P9_08") (class "Default")
      (node (ref "J16") (pin "5") (pinfunction "5_5") (pintype "passive"))
      (node (ref "R8") (pin "P$2") (pinfunction "2_P$2") (pintype "passive"))
      (node (ref "U4") (pin "70") (pinfunction "P9_8_70") (pintype "bidirectional"))
    )
    (net (code "138") (name "PA_00") (class "Default")
      (node (ref "J10") (pin "P$21") (pinfunction "P$21_P$21") (pintype "bidirectional"))
      (node (ref "U4") (pin "114") (pinfunction "PA_0_114") (pintype "bidirectional"))
    )
    (net (code "139") (name "PA_01") (class "Default")
      (node (ref "J10") (pin "P$22") (pinfunction "P$22_P$22") (pintype "bidirectional"))
      (node (ref "U4") (pin "113") (pinfunction "PA_1_113") (pintype "bidirectional"))
    )
    (net (code "140") (name "PA_08") (class "Default")
      (node (ref "J10") (pin "P$25") (pinfunction "P$25_P$25") (pintype "bidirectional"))
      (node (ref "U4") (pin "107") (pinfunction "PA_8_107") (pintype "bidirectional"))
    )
    (net (code "141") (name "PA_09") (class "Default")
      (node (ref "J10") (pin "P$24") (pinfunction "P$24_P$24") (pintype "bidirectional"))
      (node (ref "U4") (pin "108") (pinfunction "PA_9_108") (pintype "bidirectional"))
    )
    (net (code "142") (name "PA_10") (class "Default")
      (node (ref "J10") (pin "P$23") (pinfunction "P$23_P$23") (pintype "bidirectional"))
      (node (ref "U4") (pin "109") (pinfunction "PA_10_109") (pintype "bidirectional"))
    )
    (net (code "143") (name "R51") (class "Default")
      (node (ref "J4") (pin "12") (pinfunction "YHI_12") (pintype "bidirectional"))
      (node (ref "R23") (pin "P$1") (pinfunction "1_P$1") (pintype "passive"))
    )
    (net (code "144") (name "R52") (class "Default")
      (node (ref "J4") (pin "9") (pinfunction "GHI_9") (pintype "bidirectional"))
      (node (ref "R24") (pin "P$1") (pinfunction "1_P$1") (pintype "passive"))
    )
    (net (code "145") (name "RELAY_0") (class "Default")
      (node (ref "RYS6") (pin "P$1") (pinfunction "1_P$1") (pintype "passive"))
      (node (ref "U4") (pin "59") (pinfunction "P9_1_59") (pintype "bidirectional"))
    )
    (net (code "146") (name "RELAY_1") (class "Default")
      (node (ref "RZS3") (pin "P$1") (pinfunction "1_P$1") (pintype "passive"))
      (node (ref "U4") (pin "58") (pinfunction "P9_0_58") (pintype "bidirectional"))
    )
    (net (code "147") (name "RELAY_2") (class "Default")
      (node (ref "RYS5") (pin "P$1") (pinfunction "1_P$1") (pintype "passive"))
      (node (ref "U4") (pin "57") (pinfunction "P3_15_57") (pintype "bidirectional"))
    )
    (net (code "148") (name "RELAY_3") (class "Default")
      (node (ref "RXS3") (pin "P$1") (pinfunction "1_P$1") (pintype "passive"))
      (node (ref "U4") (pin "56") (pinfunction "P3_14_56") (pintype "bidirectional"))
    )
    (net (code "149") (name "RELAY_4") (class "Default")
      (node (ref "RYS16") (pin "P$1") (pinfunction "1_P$1") (pintype "passive"))
      (node (ref "U4") (pin "55") (pinfunction "P3_13_55") (pintype "bidirectional"))
    )
    (net (code "150") (name "RELAY_5") (class "Default")
      (node (ref "RZS8") (pin "P$1") (pinfunction "1_P$1") (pintype "passive"))
      (node (ref "U4") (pin "52") (pinfunction "P2_4_52") (pintype "bidirectional"))
    )
    (net (code "151") (name "RELAY_6") (class "Default")
      (node (ref "RYS15") (pin "P$1") (pinfunction "1_P$1") (pintype "passive"))
      (node (ref "U4") (pin "51") (pinfunction "P2_5_51") (pintype "bidirectional"))
    )
    (net (code "152") (name "RELAY_7") (class "Default")
      (node (ref "RXS8") (pin "P$1") (pinfunction "1_P$1") (pintype "passive"))
      (node (ref "U4") (pin "50") (pinfunction "P2_6_50") (pintype "bidirectional"))
    )
    (net (code "153") (name "RESET") (class "Default")
      (node (ref "C57") (pin "P$1") (pinfunction "1_P$1") (pintype "passive"))
      (node (ref "J11") (pin "9") (pinfunction "9_9") (pintype "passive"))
      (node (ref "R18") (pin "P$1") (pinfunction "1_P$1") (pintype "passive"))
      (node (ref "U4") (pin "67") (pinfunction "RES#_67") (pintype "bidirectional"))
    )
    (net (code "154") (name "REXT") (class "Default")
      (node (ref "C47") (pin "P$1") (pinfunction "1_P$1") (pintype "passive"))
      (node (ref "R25") (pin "P$2") (pinfunction "2_P$2") (pintype "passive"))
      (node (ref "U3") (pin "9") (pinfunction "REXT_9") (pintype "input"))
    )
    (net (code "155") (name "RXD0") (class "Default")
      (node (ref "R31") (pin "P$2") (pinfunction "2_P$2") (pintype "passive"))
      (node (ref "U3") (pin "13") (pinfunction "RXD0_13") (pintype "bidirectional"))
    )
    (net (code "156") (name "RXD1") (class "Default")
      (node (ref "R30") (pin "P$2") (pinfunction "2_P$2") (pintype "passive"))
      (node (ref "U3") (pin "12") (pinfunction "RXD1_12") (pintype "bidirectional"))
    )
    (net (code "157") (name "RXER") (class "Default")
      (node (ref "R32") (pin "P$2") (pinfunction "2_P$2") (pintype "passive"))
      (node (ref "U3") (pin "17") (pinfunction "RXER_17") (pintype "bidirectional"))
    )
    (net (code "158") (name "RXM") (class "Default")
      (node (ref "J4") (pin "6") (pinfunction "RD-_6") (pintype "bidirectional"))
      (node (ref "U3") (pin "3") (pinfunction "RXM_3") (pintype "bidirectional"))
    )
    (net (code "159") (name "RXP") (class "Default")
      (node (ref "J4") (pin "3") (pinfunction "RD+_3") (pintype "bidirectional"))
      (node (ref "U3") (pin "4") (pinfunction "RXP_4") (pintype "bidirectional"))
    )
    (net (code "160") (name "SD1_CD") (class "Default")
      (node (ref "J9") (pin "10") (pinfunction "CD_SWITCH2_10") (pintype "bidirectional"))
      (node (ref "U4") (pin "146") (pinfunction "P5_6/AN019_146") (pintype "bidirectional"))
    )
    (net (code "161") (name "SD1_CLK") (class "Default")
      (node (ref "J9") (pin "5") (pinfunction "CLOCK_5") (pintype "bidirectional"))
      (node (ref "U4") (pin "140") (pinfunction "P5_0/AN016_140") (pintype "bidirectional"))
    )
    (net (code "162") (name "SD1_CMD") (class "Default")
      (node (ref "J9") (pin "3") (pinfunction "COMMAND/RESPONSE_3") (pintype "bidirectional"))
      (node (ref "U4") (pin "141") (pinfunction "P5_1/AN116_141") (pintype "bidirectional"))
    )
    (net (code "163") (name "SD1_DAT0") (class "Default")
      (node (ref "J9") (pin "7") (pinfunction "DATA_LINE[BIT_0]_7") (pintype "bidirectional"))
      (node (ref "U4") (pin "142") (pinfunction "P5_2/AN017_142") (pintype "bidirectional"))
    )
    (net (code "164") (name "SD1_DAT1") (class "Default")
      (node (ref "J9") (pin "8") (pinfunction "DATA_LINE[BIT_1]_8") (pintype "bidirectional"))
      (node (ref "U4") (pin "143") (pinfunction "P5_3/AN117_143") (pintype "bidirectional"))
    )
    (net (code "165") (name "SD1_DAT2") (class "Default")
      (node (ref "J9") (pin "1") (pinfunction "DATA_LINE[BIT_2]_1") (pintype "bidirectional"))
      (node (ref "U4") (pin "144") (pinfunction "P5_4/AN018_144") (pintype "bidirectional"))
    )
    (net (code "166") (name "SD1_DAT3") (class "Default")
      (node (ref "J9") (pin "2") (pinfunction "CARD_DETECT/DATA_LINE[BIT_3]_2") (pintype "bidirectional"))
      (node (ref "U4") (pin "145") (pinfunction "P5_5/AN118_145") (pintype "bidirectional"))
    )
    (net (code "167") (name "SD1_WP") (class "Default")
      (node (ref "J9") (pin "9") (pinfunction "CD_SWITCH1_9") (pintype "bidirectional"))
      (node (ref "U4") (pin "147") (pinfunction "P5_7/AN119_147") (pintype "bidirectional"))
    )
    (net (code "168") (name "TCK") (class "Default")
      (node (ref "J11") (pin "7") (pinfunction "7_7") (pintype "passive"))
      (node (ref "U4") (pin "88") (pinfunction "P3_0_88") (pintype "bidirectional"))
    )
    (net (code "169") (name "TDI") (class "Default")
      (node (ref "J11") (pin "1") (pinfunction "1_1") (pintype "passive"))
      (node (ref "U4") (pin "91") (pinfunction "P1_10_91") (pintype "bidirectional"))
    )
    (net (code "170") (name "TDO") (class "Default")
      (node (ref "J11") (pin "3") (pinfunction "3_3") (pintype "passive"))
      (node (ref "U4") (pin "90") (pinfunction "P1_9_90") (pintype "bidirectional"))
    )
    (net (code "171") (name "TMS") (class "Default")
      (node (ref "J11") (pin "5") (pinfunction "5_5") (pintype "passive"))
      (node (ref "U4") (pin "89") (pinfunction "P1_8_89") (pintype "bidirectional"))
    )
    (net (code "172") (name "TXM") (class "Default")
      (node (ref "J4") (pin "2") (pinfunction "TD-_2") (pintype "bidirectional"))
      (node (ref "U3") (pin "5") (pinfunction "TXM_5") (pintype "bidirectional"))
    )
    (net (code "173") (name "TXP") (class "Default")
      (node (ref "J4") (pin "1") (pinfunction "TD+_1") (pintype "bidirectional"))
      (node (ref "U3") (pin "6") (pinfunction "TXP_6") (pintype "bidirectional"))
    )
    (net (code "174") (name "USBHS_FAULT") (class "Default")
      (node (ref "R12") (pin "P$1") (pinfunction "1_P$1") (pintype "passive"))
      (node (ref "U2") (pin "3") (pinfunction "FLG_3") (pintype "input"))
      (node (ref "U4") (pin "78") (pinfunction "P3_8_78") (pintype "bidirectional"))
    )
    (net (code "175") (name "USBHS_N") (class "Default")
      (node (ref "J3") (pin "D-") (pinfunction "D-_D-") (pintype "bidirectional"))
      (node (ref "U4") (pin "31") (pinfunction "USBHS_DM_31") (pintype "bidirectional"))
    )
    (net (code "176") (name "USBHS_P") (class "Default")
      (node (ref "J3") (pin "D+") (pinfunction "D+_D+") (pintype "bidirectional"))
      (node (ref "U4") (pin "32") (pinfunction "USBHS_DP_32") (pintype "bidirectional"))
    )
    (net (code "177") (name "USBHS_VBUS") (class "Default")
      (node (ref "C11") (pin "P$1") (pinfunction "1_P$1") (pintype "passive"))
      (node (ref "C15") (pin "1") (pinfunction "1_1") (pintype "passive"))
      (node (ref "J3") (pin "VBUS") (pinfunction "VBUS_VBUS") (pintype "power_in"))
      (node (ref "U2") (pin "5") (pinfunction "OUT_5") (pintype "input"))
      (node (ref "U4") (pin "17") (pinfunction "PB_1_17") (pintype "bidirectional"))
    )
    (net (code "178") (name "USBHS_VBUSEN") (class "Default")
      (node (ref "R1") (pin "P$1") (pinfunction "1_P$1") (pintype "passive"))
      (node (ref "U2") (pin "1") (pinfunction "EN_1") (pintype "input"))
    )
    (net (code "179") (name "USB_N") (class "Default")
      (node (ref "R5") (pin "P$1") (pinfunction "1_P$1") (pintype "passive"))
      (node (ref "U4") (pin "46") (pinfunction "USB_DM_46") (pintype "bidirectional"))
    )
    (net (code "180") (name "USB_P") (class "Default")
      (node (ref "R6") (pin "P$1") (pinfunction "1_P$1") (pintype "passive"))
      (node (ref "U4") (pin "47") (pinfunction "USB_DP_47") (pintype "bidirectional"))
    )
    (net (code "181") (name "USB_VBUS_B") (class "Default")
      (node (ref "R4") (pin "P$1") (pinfunction "1_P$1") (pintype "passive"))
      (node (ref "U4") (pin "44") (pinfunction "P4_7_44") (pintype "bidirectional"))
    )
    (net (code "182") (name "VCL_F(FLASH)") (class "Default")
      (node (ref "C36") (pin "P$2") (pinfunction "2_P$2") (pintype "passive"))
      (node (ref "U4") (pin "112") (pinfunction "VCL_F(FLASH)_112") (pintype "bidirectional"))
    )
    (net (code "183") (name "VDD") (class "Default")
      (node (ref "C10") (pin "P$2") (pinfunction "2_P$2") (pintype "passive"))
      (node (ref "C13") (pin "P$2") (pinfunction "2_P$2") (pintype "passive"))
      (node (ref "C14") (pin "P$2") (pinfunction "2_P$2") (pintype "passive"))
      (node (ref "C30") (pin "P$2") (pinfunction "2_P$2") (pintype "passive"))
      (node (ref "C32") (pin "P$1") (pinfunction "1_P$1") (pintype "passive"))
      (node (ref "C33") (pin "P$1") (pinfunction "1_P$1") (pintype "passive"))
      (node (ref "C34") (pin "P$1") (pinfunction "1_P$1") (pintype "passive"))
      (node (ref "C35") (pin "P$1") (pinfunction "1_P$1") (pintype "passive"))
      (node (ref "C48") (pin "1") (pinfunction "1_1") (pintype "passive"))
      (node (ref "C49") (pin "P$1") (pinfunction "1_P$1") (pintype "passive"))
      (node (ref "C54") (pin "P$2") (pinfunction "2_P$2") (pintype "passive"))
      (node (ref "C55") (pin "P$2") (pinfunction "2_P$2") (pintype "passive"))
      (node (ref "C56") (pin "P$2") (pinfunction "2_P$2") (pintype "passive"))
      (node (ref "C58") (pin "P$1") (pinfunction "1_P$1") (pintype "passive"))
      (node (ref "C59") (pin "P$1") (pinfunction "1_P$1") (pintype "passive"))
      (node (ref "C60") (pin "P$1") (pinfunction "1_P$1") (pintype "passive"))
      (node (ref "C61") (pin "P$2") (pinfunction "2_P$2") (pintype "passive"))
      (node (ref "FB2/2") (pin "1") (pinfunction "P$1_1") (pintype "bidirectional"))
      (node (ref "J11") (pin "2") (pinfunction "2_2") (pintype "passive"))
      (node (ref "J11") (pin "4") (pinfunction "4_4") (pintype "passive"))
      (node (ref "J9") (pin "4") (pinfunction "SUPPLY_VOLTAGE_4") (pintype "power_in"))
      (node (ref "L3") (pin "2") (pinfunction "P$2_2") (pintype "bidirectional"))
      (node (ref "R10") (pin "P$1") (pinfunction "1_P$1") (pintype "passive"))
      (node (ref "R11") (pin "P$1") (pinfunction "1_P$1") (pintype "passive"))
      (node (ref "R13") (pin "P$2") (pinfunction "2_P$2") (pintype "passive"))
      (node (ref "R14") (pin "P$1") (pinfunction "1_P$1") (pintype "passive"))
      (node (ref "R18") (pin "P$2") (pinfunction "2_P$2") (pintype "passive"))
      (node (ref "R2") (pin "P$1") (pinfunction "1_P$1") (pintype "passive"))
      (node (ref "R20") (pin "P$1") (pinfunction "1_P$1") (pintype "passive"))
      (node (ref "R21") (pin "P$1") (pinfunction "1_P$1") (pintype "passive"))
      (node (ref "R23") (pin "P$2") (pinfunction "2_P$2") (pintype "passive"))
      (node (ref "R24") (pin "P$2") (pinfunction "2_P$2") (pintype "passive"))
      (node (ref "R26") (pin "P$2") (pinfunction "2_P$2") (pintype "passive"))
      (node (ref "R27") (pin "P$2") (pinfunction "2_P$2") (pintype "passive"))
      (node (ref "R28") (pin "P$2") (pinfunction "2_P$2") (pintype "passive"))
      (node (ref "R29") (pin "P$2") (pinfunction "2_P$2") (pintype "passive"))
      (node (ref "R3") (pin "P$1") (pinfunction "1_P$1") (pintype "passive"))
      (node (ref "R8") (pin "P$1") (pinfunction "1_P$1") (pintype "passive"))
      (node (ref "R9") (pin "P$1") (pinfunction "1_P$1") (pintype "passive"))
      (node (ref "U3") (pin "14") (pinfunction "VDDIO_14") (pintype "power_in"))
      (node (ref "U4") (pin "110") (pinfunction "VCC(IO)5_110") (pintype "bidirectional"))
      (node (ref "U4") (pin "123") (pinfunction "VCC(IO)6_123") (pintype "bidirectional"))
      (node (ref "U4") (pin "138") (pinfunction "VCC(IO)7_138") (pintype "bidirectional"))
      (node (ref "U4") (pin "149") (pinfunction "VCC(IO)8_149") (pintype "bidirectional"))
      (node (ref "U4") (pin "155") (pinfunction "AVCC0_155") (pintype "bidirectional"))
      (node (ref "U4") (pin "171") (pinfunction "VCC(IO)9_171") (pintype "bidirectional"))
      (node (ref "U4") (pin "25") (pinfunction "VCC1_25") (pintype "bidirectional"))
      (node (ref "U4") (pin "26") (pinfunction "AVCC_SUBHS_26") (pintype "bidirectional"))
      (node (ref "U4") (pin "34") (pinfunction "VCC_USBHS_34") (pintype "bidirectional"))
      (node (ref "U4") (pin "48") (pinfunction "VCC_USB_48") (pintype "bidirectional"))
      (node (ref "U4") (pin "61") (pinfunction "VCC(IO)2_61") (pintype "bidirectional"))
      (node (ref "U4") (pin "84") (pinfunction "VCC(IO)3_84") (pintype "bidirectional"))
      (node (ref "U4") (pin "97") (pinfunction "VCC(IO)4_97") (pintype "bidirectional"))
    )
    (net (code "184") (name "VDD5") (class "Default")
      (node (ref "C5") (pin "P$1") (pinfunction "1_P$1") (pintype "passive"))
      (node (ref "C8") (pin "P$1") (pinfunction "1_P$1") (pintype "passive"))
      (node (ref "J1") (pin "5") (pinfunction "5_5") (pintype "passive"))
      (node (ref "J1") (pin "6") (pinfunction "6_6") (pintype "passive"))
      (node (ref "R1") (pin "P$2") (pinfunction "2_P$2") (pintype "passive"))
      (node (ref "R12") (pin "P$2") (pinfunction "2_P$2") (pintype "passive"))
      (node (ref "U2") (pin "4") (pinfunction "VIN_4") (pintype "input"))
    )
    (net (code "185") (name "VDD12") (class "Default")
      (node (ref "J1") (pin "7") (pinfunction "7_7") (pintype "passive"))
      (node (ref "J1") (pin "8") (pinfunction "8_8") (pintype "passive"))
    )
    (net (code "186") (name "VDDIN") (class "Default")
      (node (ref "J1") (pin "3") (pinfunction "3_3") (pintype "passive"))
      (node (ref "J1") (pin "4") (pinfunction "4_4") (pintype "passive"))
      (node (ref "L3") (pin "1") (pinfunction "P$1_1") (pintype "bidirectional"))
    )
    (net (code "187") (name "VDD_1.2") (class "Default")
      (node (ref "C45") (pin "P$1") (pinfunction "1_P$1") (pintype "passive"))
      (node (ref "C46") (pin "P$1") (pinfunction "1_P$1") (pintype "passive"))
      (node (ref "U3") (pin "1") (pinfunction "VDD_1.2_1") (pintype "power_in"))
    )
    (net (code "188") (name "XCIN") (class "Default")
      (node (ref "C50") (pin "P$1") (pinfunction "1_P$1") (pintype "passive"))
      (node (ref "U4") (pin "20") (pinfunction "XCIN_20") (pintype "bidirectional"))
      (node (ref "X3") (pin "P$1") (pinfunction "P$1_P$1") (pintype "bidirectional"))
    )
    (net (code "189") (name "XCOUT") (class "Default")
      (node (ref "C51") (pin "P$1") (pinfunction "1_P$1") (pintype "passive"))
      (node (ref "U4") (pin "21") (pinfunction "XCOUT_21") (pintype "bidirectional"))
      (node (ref "X3") (pin "P$2") (pinfunction "P$2_P$2") (pintype "bidirectional"))
    )
    (net (code "190") (name "XII") (class "Default")
      (node (ref "C42") (pin "P$1") (pinfunction "1_P$1") (pintype "passive"))
      (node (ref "U$3") (pin "1") (pinfunction "1_1") (pintype "bidirectional"))
      (node (ref "U3") (pin "8") (pinfunction "XI_8") (pintype "input"))
    )
    (net (code "191") (name "XOO") (class "Default")
      (node (ref "C41") (pin "P$1") (pinfunction "1_P$1") (pintype "passive"))
      (node (ref "U$3") (pin "3") (pinfunction "3_3") (pintype "bidirectional"))
      (node (ref "U3") (pin "7") (pinfunction "XO_7") (pintype "output"))
    )
    (net (code "192") (name "XTAL1") (class "Default")
      (node (ref "C52") (pin "P$1") (pinfunction "1_P$1") (pintype "passive"))
      (node (ref "U4") (pin "23") (pinfunction "P2_13/XTAL_23") (pintype "bidirectional"))
      (node (ref "X4") (pin "1") (pinfunction "1_1") (pintype "bidirectional"))
    )
    (net (code "193") (name "XTAL2") (class "Default")
      (node (ref "C53") (pin "P$1") (pinfunction "1_P$1") (pintype "passive"))
      (node (ref "U4") (pin "24") (pinfunction "P2_12/EXTAL_24") (pintype "bidirectional"))
      (node (ref "X4") (pin "3") (pinfunction "3_3") (pintype "bidirectional"))
    )
    (net (code "194") (name "unconnected-(U4-VBAT-Pad18)") (class "Default")
      (node (ref "U4") (pin "18") (pinfunction "VBAT_18") (pintype "bidirectional"))
    )
    (net (code "195") (name "unconnected-(U4-VREFH-Pad154)") (class "Default")
      (node (ref "U4") (pin "154") (pinfunction "VREFH_154") (pintype "bidirectional"))
    )
    (net (code "196") (name "unconnected-(U4-VREFH0-Pad158)") (class "Default")
      (node (ref "U4") (pin "158") (pinfunction "VREFH0_158") (pintype "bidirectional"))
    )
    (net (code "197") (name "unconnected-(U4-VREFL-Pad153)") (class "Default")
      (node (ref "U4") (pin "153") (pinfunction "VREFL_153") (pintype "bidirectional"))
    )
    (net (code "198") (name "unconnected-(U4-VREFL0-Pad157)") (class "Default")
      (node (ref "U4") (pin "157") (pinfunction "VREFL0_157") (pintype "bidirectional"))
    )
  )
)
